# OOBDpiZero.net
KiCad netlist of a schematic drawn in EAGLE
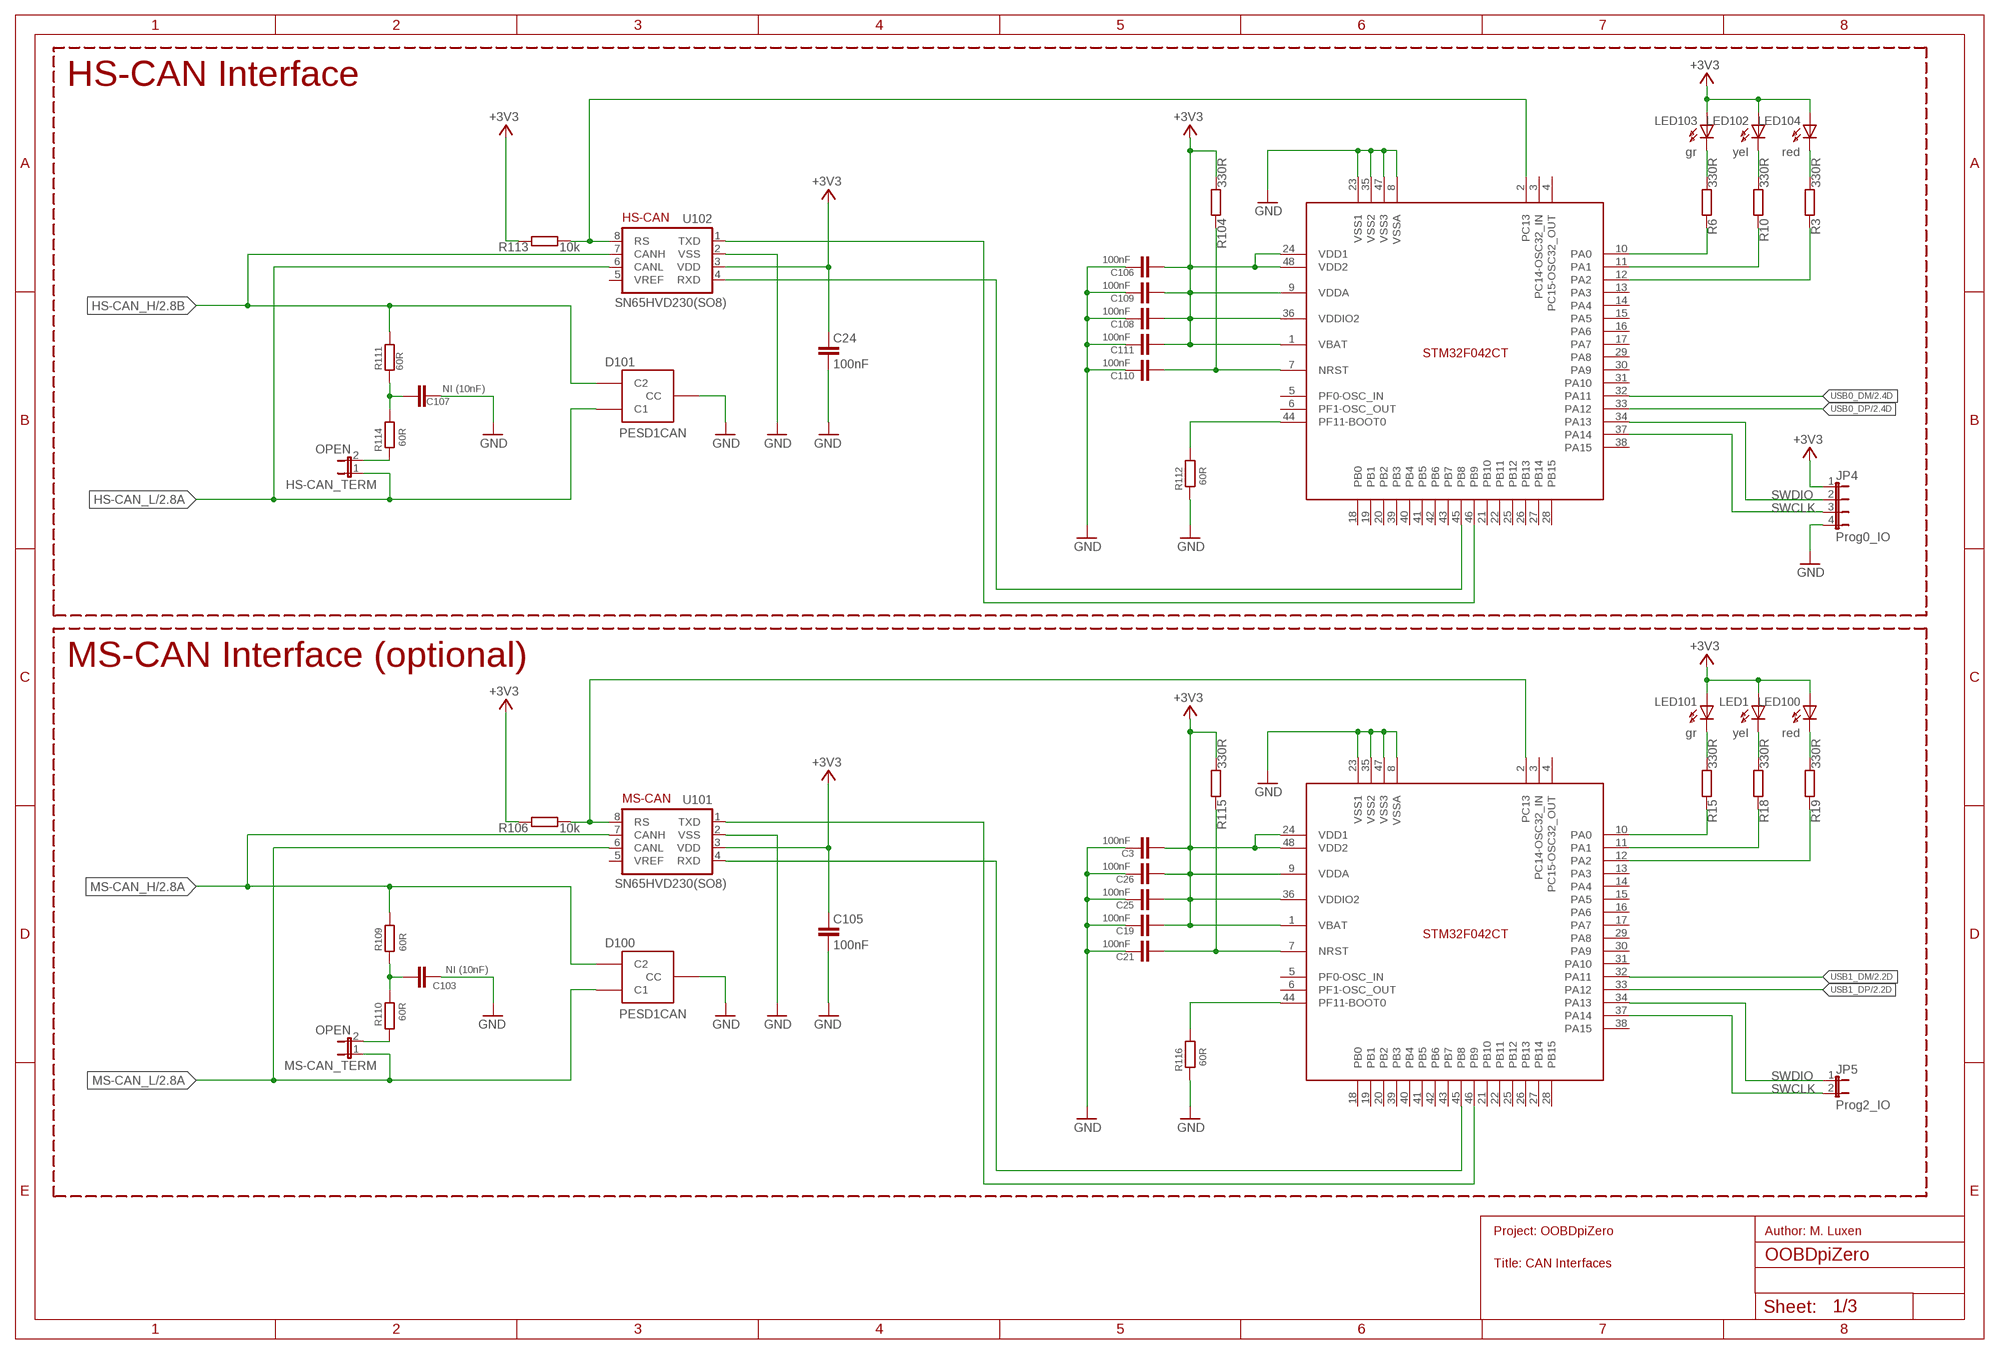
[diagram p0: schematic, sheet 1]
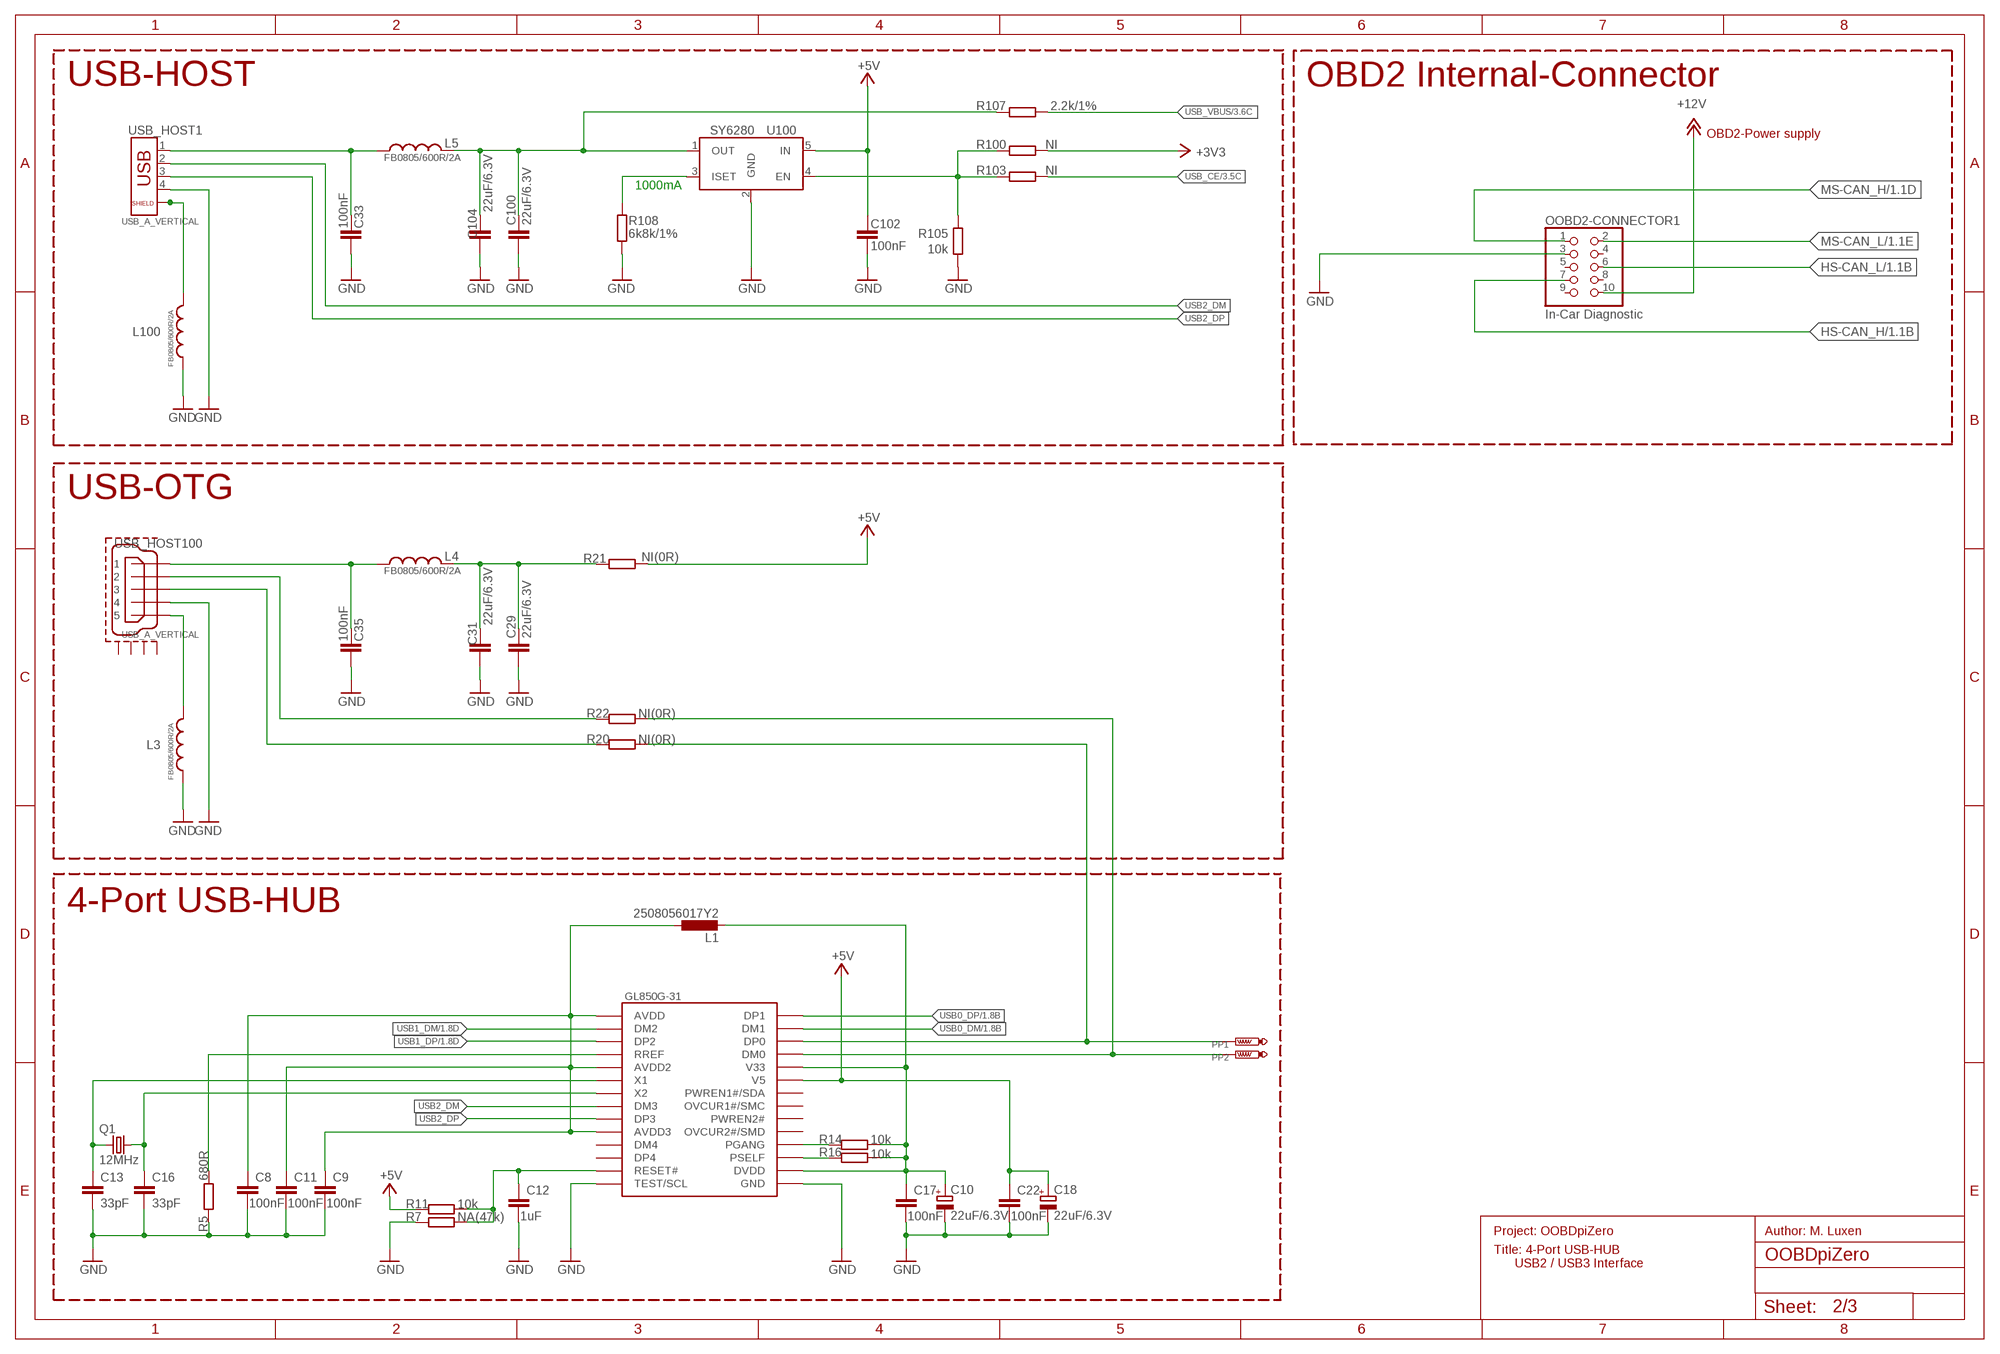
[diagram p1: schematic, sheet 2]
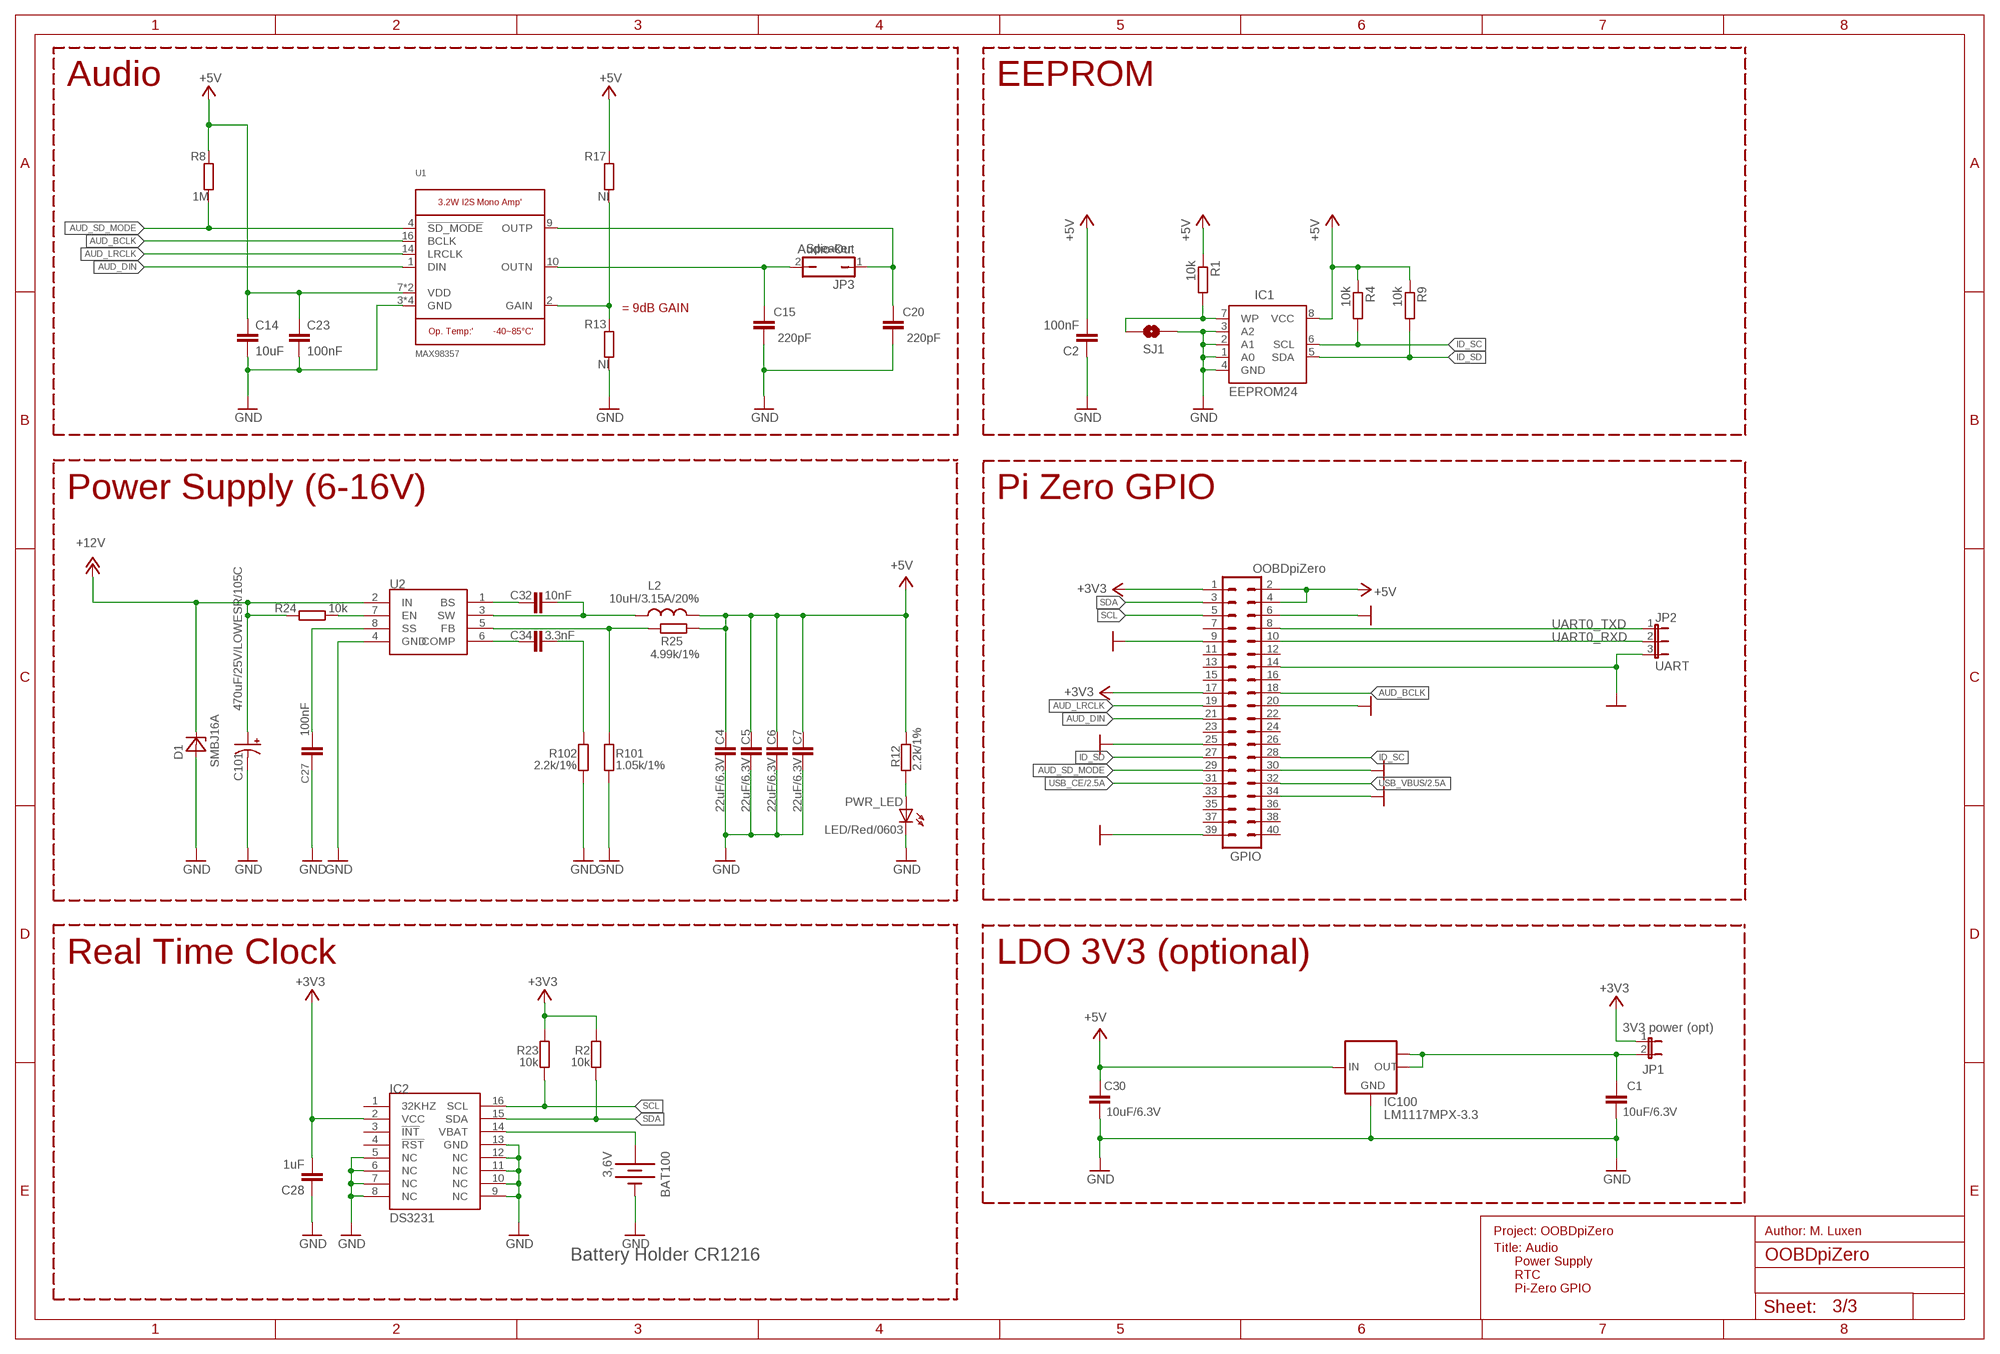
[diagram p2: schematic, sheet 3]

(export (version "E")
  (design (tool "Eeschema 10.0.6"))
  (components
    (comp (ref "BAT100")
      (value "3,6V")
      (footprint "eagle-import:BATTCON_12MM_PTH")
      (libsource (lib "eagle-import") (part "BATTERY12PTH"))
    )
    (comp (ref "C1")
      (value "10uF/6.3V")
      (footprint "eagle-import:C0603")
      (libsource (lib "eagle-import") (part "C-EUC0603"))
    )
    (comp (ref "C2")
      (value "100nF")
      (footprint "eagle-import:C0603")
      (libsource (lib "eagle-import") (part "C-EUC0603"))
    )
    (comp (ref "C4")
      (value "22uF/6.3V")
      (footprint "eagle-import:C0603")
      (libsource (lib "eagle-import") (part "C-EUC0603"))
    )
    (comp (ref "C5")
      (value "22uF/6.3V")
      (footprint "eagle-import:C0603")
      (libsource (lib "eagle-import") (part "C-EUC0603"))
    )
    (comp (ref "C6")
      (value "22uF/6.3V")
      (footprint "eagle-import:C0603")
      (libsource (lib "eagle-import") (part "C-EUC0603"))
    )
    (comp (ref "C7")
      (value "22uF/6.3V")
      (footprint "eagle-import:C0603")
      (libsource (lib "eagle-import") (part "C-EUC0603"))
    )
    (comp (ref "C14")
      (value "10uF")
      (footprint "eagle-import:C0805K")
      (libsource (lib "eagle-import") (part "C-EUC0805K"))
    )
    (comp (ref "C15")
      (value "220pF")
      (footprint "eagle-import:C0603K")
      (libsource (lib "eagle-import") (part "C-EUC0603K"))
    )
    (comp (ref "C20")
      (value "220pF")
      (footprint "eagle-import:C0603K")
      (libsource (lib "eagle-import") (part "C-EUC0603K"))
    )
    (comp (ref "C23")
      (value "100nF")
      (footprint "eagle-import:C0603K")
      (libsource (lib "eagle-import") (part "C-EUC0603K"))
    )
    (comp (ref "C27")
      (value "100nF")
      (footprint "eagle-import:C0603")
      (libsource (lib "eagle-import") (part "C-EUC0603"))
    )
    (comp (ref "C28")
      (value "1uF")
      (footprint "eagle-import:C0603")
      (libsource (lib "eagle-import") (part "C-EUC0603"))
    )
    (comp (ref "C30")
      (value "10uF/6.3V")
      (footprint "eagle-import:C0603")
      (libsource (lib "eagle-import") (part "C-EUC0603"))
    )
    (comp (ref "C32")
      (value "10nF")
      (footprint "eagle-import:C0603")
      (libsource (lib "eagle-import") (part "C-EUC0603"))
    )
    (comp (ref "C34")
      (value "3.3nF")
      (footprint "eagle-import:C0603")
      (libsource (lib "eagle-import") (part "C-EUC0603"))
    )
    (comp (ref "C101")
      (value "470uF/25V/LOWESR/105C")
      (footprint "eagle-import:PANASONIC_D")
      (libsource (lib "eagle-import") (part "47UF-50V-20%(ELECT)"))
    )
    (comp (ref "D1")
      (value "SMBJ16A")
      (footprint "eagle-import:DO214AA")
      (libsource (lib "eagle-import") (part "SMBJ16A"))
    )
    (comp (ref "GPIO")
      (value "OOBDpiZero")
      (footprint "eagle-import:PIZERO_THOUGH_HOLE")
      (libsource (lib "eagle-import") (part "PIZERO_THROUGH_HOLE"))
    )
    (comp (ref "IC1")
      (value "EEPROM24")
      (footprint "eagle-import:SOIC8")
      (libsource (lib "eagle-import") (part "EEPROM24"))
    )
    (comp (ref "IC2")
      (value "DS3231")
      (footprint "eagle-import:SOIC-16W")
      (libsource (lib "eagle-import") (part "DS3231SOIC-16W"))
    )
    (comp (ref "IC100")
      (value "LM1117MPX-3.3")
      (footprint "eagle-import:SOT223")
      (libsource (lib "eagle-import") (part "LM1117MPX-3.3"))
    )
    (comp (ref "JP1")
      (value "3V3 power (opt)")
      (footprint "eagle-import:JP1")
      (libsource (lib "eagle-import") (part "JP1E"))
    )
    (comp (ref "JP2")
      (value "UART")
      (footprint "eagle-import:JP2")
      (libsource (lib "eagle-import") (part "JP2E"))
    )
    (comp (ref "JP3")
      (value "Audio-Out")
      (footprint "eagle-import:JP1")
      (libsource (lib "eagle-import") (part "JP1Q"))
    )
    (comp (ref "L2")
      (value "10uH/3.15A/20%")
      (footprint "eagle-import:8X8MM_3131")
      (libsource (lib "eagle-import") (part "LLQH88PN100M38"))
    )
    (comp (ref "PWR_LED")
      (value "LED/Red/0603")
      (footprint "eagle-import:LED-0603")
      (libsource (lib "eagle-import") (part "LED0603DWS"))
    )
    (comp (ref "R1")
      (value "10k")
      (footprint "eagle-import:R0603")
      (libsource (lib "eagle-import") (part "R-EU_R0603"))
    )
    (comp (ref "R2")
      (value "10k")
      (footprint "eagle-import:R0603")
      (libsource (lib "eagle-import") (part "R-EU_R0603"))
    )
    (comp (ref "R4")
      (value "10k")
      (footprint "eagle-import:R0603")
      (libsource (lib "eagle-import") (part "R-EU_R0603"))
    )
    (comp (ref "R8")
      (value "1M")
      (footprint "eagle-import:R0603")
      (libsource (lib "eagle-import") (part "resistor_R-EU_R0603"))
    )
    (comp (ref "R9")
      (value "10k")
      (footprint "eagle-import:R0603")
      (libsource (lib "eagle-import") (part "R-EU_R0603"))
    )
    (comp (ref "R12")
      (value "2.2k/1%")
      (footprint "eagle-import:R0603")
      (libsource (lib "eagle-import") (part "R-EU_R0603"))
    )
    (comp (ref "R13")
      (value "NI")
      (footprint "eagle-import:R0603")
      (libsource (lib "eagle-import") (part "resistor_R-EU_R0603"))
    )
    (comp (ref "R17")
      (value "NI")
      (footprint "eagle-import:R0603")
      (libsource (lib "eagle-import") (part "resistor_R-EU_R0603"))
    )
    (comp (ref "R23")
      (value "10k")
      (footprint "eagle-import:R0603")
      (libsource (lib "eagle-import") (part "R-EU_R0603"))
    )
    (comp (ref "R24")
      (value "10k")
      (footprint "eagle-import:R0603")
      (libsource (lib "eagle-import") (part "R-EU_R0603"))
    )
    (comp (ref "R25")
      (value "4.99k/1%")
      (footprint "eagle-import:R0603")
      (libsource (lib "eagle-import") (part "R-EU_R0603"))
    )
    (comp (ref "R101")
      (value "1.05k/1%")
      (footprint "eagle-import:R0603")
      (libsource (lib "eagle-import") (part "R-EU_R0603"))
    )
    (comp (ref "R102")
      (value "2.2k/1%")
      (footprint "eagle-import:R0603")
      (libsource (lib "eagle-import") (part "R-EU_R0603"))
    )
    (comp (ref "SJ1")
      (value "SOLDERJUMPERTRACE")
      (footprint "eagle-import:SJ_2S-TRACE")
      (libsource (lib "eagle-import") (part "SOLDERJUMPERTRACE"))
    )
    (comp (ref "U1")
      (value "MAX98357")
      (footprint "eagle-import:QFN16_3MM")
      (libsource (lib "eagle-import") (part "AUDIOAMP_MAX98357"))
    )
    (comp (ref "U2")
      (value "MP1482")
      (footprint "eagle-import:SOIC8")
      (libsource (lib "eagle-import") (part "MP1482"))
    )
    (comp (ref "C8")
      (value "100nF")
      (footprint "eagle-import:C0603")
      (libsource (lib "eagle-import") (part "resistor_C-EUC0603"))
    )
    (comp (ref "C9")
      (value "100nF")
      (footprint "eagle-import:C0603")
      (libsource (lib "eagle-import") (part "resistor_C-EUC0603"))
    )
    (comp (ref "C10")
      (value "22uF/6.3V")
      (footprint "eagle-import:SMC_A")
      (libsource (lib "eagle-import") (part "CPOL-EUSMCA"))
    )
    (comp (ref "C11")
      (value "100nF")
      (footprint "eagle-import:C0603")
      (libsource (lib "eagle-import") (part "resistor_C-EUC0603"))
    )
    (comp (ref "C12")
      (value "1uF")
      (footprint "eagle-import:C0603")
      (libsource (lib "eagle-import") (part "resistor_C-EUC0603"))
    )
    (comp (ref "C13")
      (value "33pF")
      (footprint "eagle-import:C0603")
      (libsource (lib "eagle-import") (part "resistor_C-EUC0603"))
    )
    (comp (ref "C16")
      (value "33pF")
      (footprint "eagle-import:C0603")
      (libsource (lib "eagle-import") (part "resistor_C-EUC0603"))
    )
    (comp (ref "C17")
      (value "100nF")
      (footprint "eagle-import:C0603")
      (libsource (lib "eagle-import") (part "resistor_C-EUC0603"))
    )
    (comp (ref "C18")
      (value "22uF/6.3V")
      (footprint "eagle-import:SMC_A")
      (libsource (lib "eagle-import") (part "CPOL-EUSMCA"))
    )
    (comp (ref "C22")
      (value "100nF")
      (footprint "eagle-import:C0603")
      (libsource (lib "eagle-import") (part "resistor_C-EUC0603"))
    )
    (comp (ref "C29")
      (value "22uF/6.3V")
      (footprint "eagle-import:C0603")
      (libsource (lib "eagle-import") (part "C-EUC0603"))
    )
    (comp (ref "C31")
      (value "22uF/6.3V")
      (footprint "eagle-import:C0603")
      (libsource (lib "eagle-import") (part "C-EUC0603"))
    )
    (comp (ref "C33")
      (value "100nF")
      (footprint "eagle-import:C0603K")
      (libsource (lib "eagle-import") (part "C-EUC0603K"))
    )
    (comp (ref "C35")
      (value "100nF")
      (footprint "eagle-import:C0603K")
      (libsource (lib "eagle-import") (part "C-EUC0603K"))
    )
    (comp (ref "C100")
      (value "22uF/6.3V")
      (footprint "eagle-import:C0603")
      (libsource (lib "eagle-import") (part "C-EUC0603"))
    )
    (comp (ref "C102")
      (value "100nF")
      (footprint "eagle-import:C0603K")
      (libsource (lib "eagle-import") (part "C-EUC0603K"))
    )
    (comp (ref "C104")
      (value "22uF/6.3V")
      (footprint "eagle-import:C0603")
      (libsource (lib "eagle-import") (part "C-EUC0603"))
    )
    (comp (ref "L1")
      (value "2508056017Y2")
      (footprint "eagle-import:L0805@1")
      (libsource (lib "eagle-import") (part "L-EUL0805"))
    )
    (comp (ref "L3")
      (value "FB0805/600R/2A")
      (footprint "eagle-import:L0603")
      (libsource (lib "eagle-import") (part "L-USL0603"))
    )
    (comp (ref "L4")
      (value "FB0805/600R/2A")
      (footprint "eagle-import:L0603")
      (libsource (lib "eagle-import") (part "L-USL0603"))
    )
    (comp (ref "L5")
      (value "FB0805/600R/2A")
      (footprint "eagle-import:L0603")
      (libsource (lib "eagle-import") (part "L-USL0603"))
    )
    (comp (ref "L100")
      (value "FB0805/600R/2A")
      (footprint "eagle-import:L0603")
      (libsource (lib "eagle-import") (part "L-USL0603"))
    )
    (comp (ref "OOBD2-CONNECTOR1")
      (value "In-Car Diagnostic")
      (footprint "eagle-import:2X05_90")
      (libsource (lib "eagle-import") (part "PINHD-2X5/90"))
    )
    (comp (ref "PP1")
      (value "PTR1PAD1-11")
      (footprint "eagle-import:P1-11")
      (libsource (lib "eagle-import") (part "PTR1PAD1-11"))
    )
    (comp (ref "PP2")
      (value "PTR1PAD1-11")
      (footprint "eagle-import:P1-11")
      (libsource (lib "eagle-import") (part "PTR1PAD1-11"))
    )
    (comp (ref "Q1")
      (value "12MHz")
      (footprint "eagle-import:SM49")
      (libsource (lib "eagle-import") (part "CRYSTALSM49"))
    )
    (comp (ref "R5")
      (value "680R")
      (footprint "eagle-import:R0603")
      (libsource (lib "eagle-import") (part "resistor_R-EU_R0603"))
    )
    (comp (ref "R7")
      (value "NA(47k)")
      (footprint "eagle-import:R0603")
      (libsource (lib "eagle-import") (part "resistor_R-EU_R0603"))
    )
    (comp (ref "R11")
      (value "10k")
      (footprint "eagle-import:R0603")
      (libsource (lib "eagle-import") (part "resistor_R-EU_R0603"))
    )
    (comp (ref "R14")
      (value "10k")
      (footprint "eagle-import:R0603")
      (libsource (lib "eagle-import") (part "resistor_R-EU_R0603"))
    )
    (comp (ref "R16")
      (value "10k")
      (footprint "eagle-import:R0603")
      (libsource (lib "eagle-import") (part "resistor_R-EU_R0603"))
    )
    (comp (ref "R20")
      (value "NI(0R)")
      (footprint "eagle-import:R0603")
      (libsource (lib "eagle-import") (part "resistor_R-EU_R0603"))
    )
    (comp (ref "R21")
      (value "NI(0R)")
      (footprint "eagle-import:R0805")
      (libsource (lib "eagle-import") (part "resistor_R-EU_R0805"))
    )
    (comp (ref "R22")
      (value "NI(0R)")
      (footprint "eagle-import:R0603")
      (libsource (lib "eagle-import") (part "resistor_R-EU_R0603"))
    )
    (comp (ref "R100")
      (value "NI")
      (footprint "eagle-import:R0603")
      (libsource (lib "eagle-import") (part "R-EU_R0603"))
    )
    (comp (ref "R103")
      (value "NI")
      (footprint "eagle-import:R0603")
      (libsource (lib "eagle-import") (part "R-EU_R0603"))
    )
    (comp (ref "R105")
      (value "10k")
      (footprint "eagle-import:R0603")
      (libsource (lib "eagle-import") (part "R-EU_R0603"))
    )
    (comp (ref "R107")
      (value "2.2k/1%")
      (footprint "eagle-import:R0603")
      (libsource (lib "eagle-import") (part "R-EU_R0603"))
    )
    (comp (ref "R108")
      (value "6k8k/1%")
      (footprint "eagle-import:R0603")
      (libsource (lib "eagle-import") (part "R-EU_R0603"))
    )
    (comp (ref "U$101")
      (value "GL850G-31")
      (footprint "eagle-import:TSSOP28")
      (libsource (lib "eagle-import") (part "GL850G-31"))
    )
    (comp (ref "U100")
      (value "SY6280")
      (footprint "eagle-import:SOT23-5")
      (libsource (lib "eagle-import") (part "SY6280"))
    )
    (comp (ref "USB_HOST1")
      (value "USB_A_VERTICAL")
      (footprint "eagle-import:USB_PN87520_DEV_PTH")
      (libsource (lib "eagle-import") (part "USB_SHIELD1"))
    )
    (comp (ref "USB_HOST100")
      (value "USB_A_VERTICAL")
      (footprint "eagle-import:47589-0001")
      (libsource (lib "eagle-import") (part "MICRO-USB-RECEPTACLE47589-0001"))
    )
    (comp (ref "C3")
      (value "100nF")
      (footprint "eagle-import:C0603")
      (libsource (lib "eagle-import") (part "resistor_C-EUC0603"))
    )
    (comp (ref "C19")
      (value "100nF")
      (footprint "eagle-import:C0603")
      (libsource (lib "eagle-import") (part "resistor_C-EUC0603"))
    )
    (comp (ref "C21")
      (value "100nF")
      (footprint "eagle-import:C0603")
      (libsource (lib "eagle-import") (part "resistor_C-EUC0603"))
    )
    (comp (ref "C24")
      (value "100nF")
      (footprint "eagle-import:C0603K")
      (libsource (lib "eagle-import") (part "C-EUC0603K"))
    )
    (comp (ref "C25")
      (value "100nF")
      (footprint "eagle-import:C0603")
      (libsource (lib "eagle-import") (part "resistor_C-EUC0603"))
    )
    (comp (ref "C26")
      (value "100nF")
      (footprint "eagle-import:C0603")
      (libsource (lib "eagle-import") (part "resistor_C-EUC0603"))
    )
    (comp (ref "C103")
      (value "NI (10nF)")
      (footprint "eagle-import:C0603")
      (libsource (lib "eagle-import") (part "resistor_C-EUC0603"))
    )
    (comp (ref "C105")
      (value "100nF")
      (footprint "eagle-import:C0603K")
      (libsource (lib "eagle-import") (part "C-EUC0603K"))
    )
    (comp (ref "C106")
      (value "100nF")
      (footprint "eagle-import:C0603")
      (libsource (lib "eagle-import") (part "resistor_C-EUC0603"))
    )
    (comp (ref "C107")
      (value "NI (10nF)")
      (footprint "eagle-import:C0603")
      (libsource (lib "eagle-import") (part "resistor_C-EUC0603"))
    )
    (comp (ref "C108")
      (value "100nF")
      (footprint "eagle-import:C0603")
      (libsource (lib "eagle-import") (part "resistor_C-EUC0603"))
    )
    (comp (ref "C109")
      (value "100nF")
      (footprint "eagle-import:C0603")
      (libsource (lib "eagle-import") (part "resistor_C-EUC0603"))
    )
    (comp (ref "C110")
      (value "100nF")
      (footprint "eagle-import:C0603")
      (libsource (lib "eagle-import") (part "resistor_C-EUC0603"))
    )
    (comp (ref "C111")
      (value "100nF")
      (footprint "eagle-import:C0603")
      (libsource (lib "eagle-import") (part "resistor_C-EUC0603"))
    )
    (comp (ref "D100")
      (value "PESD1CAN")
      (footprint "eagle-import:SOT23")
      (libsource (lib "eagle-import") (part "PESD1CAN"))
    )
    (comp (ref "D101")
      (value "PESD1CAN")
      (footprint "eagle-import:SOT23")
      (libsource (lib "eagle-import") (part "PESD1CAN"))
    )
    (comp (ref "HS-CAN_TERM")
      (value "OPEN")
      (footprint "eagle-import:1X02")
      (libsource (lib "eagle-import") (part "JUMPER-2PTH"))
    )
    (comp (ref "JP4")
      (value "Prog0_IO")
      (footprint "eagle-import:JP4")
      (libsource (lib "eagle-import") (part "JP4E"))
    )
    (comp (ref "JP5")
      (value "Prog2_IO")
      (footprint "eagle-import:JP1")
      (libsource (lib "eagle-import") (part "JP1E"))
    )
    (comp (ref "LED1")
      (value "yel")
      (footprint "eagle-import:LED_0603")
      (libsource (lib "eagle-import") (part "LEDLED_0603"))
    )
    (comp (ref "LED100")
      (value "red")
      (footprint "eagle-import:LED_0603")
      (libsource (lib "eagle-import") (part "LEDLED_0603"))
    )
    (comp (ref "LED101")
      (value "gr")
      (footprint "eagle-import:LED_0603")
      (libsource (lib "eagle-import") (part "LEDLED_0603"))
    )
    (comp (ref "LED102")
      (value "yel")
      (footprint "eagle-import:LED_0603")
      (libsource (lib "eagle-import") (part "LEDLED_0603"))
    )
    (comp (ref "LED103")
      (value "gr")
      (footprint "eagle-import:LED_0603")
      (libsource (lib "eagle-import") (part "LEDLED_0603"))
    )
    (comp (ref "LED104")
      (value "red")
      (footprint "eagle-import:LED_0603")
      (libsource (lib "eagle-import") (part "LEDLED_0603"))
    )
    (comp (ref "MS-CAN_TERM")
      (value "OPEN")
      (footprint "eagle-import:1X02")
      (libsource (lib "eagle-import") (part "JUMPER-2PTH"))
    )
    (comp (ref "R3")
      (value "330R")
      (footprint "eagle-import:R0603")
      (libsource (lib "eagle-import") (part "R-EU_R0603"))
    )
    (comp (ref "R6")
      (value "330R")
      (footprint "eagle-import:R0603")
      (libsource (lib "eagle-import") (part "R-EU_R0603"))
    )
    (comp (ref "R10")
      (value "330R")
      (footprint "eagle-import:R0603")
      (libsource (lib "eagle-import") (part "R-EU_R0603"))
    )
    (comp (ref "R15")
      (value "330R")
      (footprint "eagle-import:R0603")
      (libsource (lib "eagle-import") (part "R-EU_R0603"))
    )
    (comp (ref "R18")
      (value "330R")
      (footprint "eagle-import:R0603")
      (libsource (lib "eagle-import") (part "R-EU_R0603"))
    )
    (comp (ref "R19")
      (value "330R")
      (footprint "eagle-import:R0603")
      (libsource (lib "eagle-import") (part "R-EU_R0603"))
    )
    (comp (ref "R104")
      (value "330R")
      (footprint "eagle-import:R0603")
      (libsource (lib "eagle-import") (part "R-EU_R0603"))
    )
    (comp (ref "R106")
      (value "10k")
      (footprint "eagle-import:R0603")
      (libsource (lib "eagle-import") (part "R-EU_R0603"))
    )
    (comp (ref "R109")
      (value "60R")
      (footprint "eagle-import:R0603")
      (libsource (lib "eagle-import") (part "resistor_R-EU_R0603"))
    )
    (comp (ref "R110")
      (value "60R")
      (footprint "eagle-import:R0603")
      (libsource (lib "eagle-import") (part "resistor_R-EU_R0603"))
    )
    (comp (ref "R111")
      (value "60R")
      (footprint "eagle-import:R0603")
      (libsource (lib "eagle-import") (part "resistor_R-EU_R0603"))
    )
    (comp (ref "R112")
      (value "60R")
      (footprint "eagle-import:R0603")
      (libsource (lib "eagle-import") (part "resistor_R-EU_R0603"))
    )
    (comp (ref "R113")
      (value "10k")
      (footprint "eagle-import:R0603")
      (libsource (lib "eagle-import") (part "R-EU_R0603"))
    )
    (comp (ref "R114")
      (value "60R")
      (footprint "eagle-import:R0603")
      (libsource (lib "eagle-import") (part "resistor_R-EU_R0603"))
    )
    (comp (ref "R115")
      (value "330R")
      (footprint "eagle-import:R0603")
      (libsource (lib "eagle-import") (part "R-EU_R0603"))
    )
    (comp (ref "R116")
      (value "60R")
      (footprint "eagle-import:R0603")
      (libsource (lib "eagle-import") (part "resistor_R-EU_R0603"))
    )
    (comp (ref "U$100")
      (value "STM32F042CT")
      (footprint "eagle-import:LQFP48")
      (libsource (lib "eagle-import") (part "STM32F042CT"))
    )
    (comp (ref "U$102")
      (value "STM32F042CT")
      (footprint "eagle-import:LQFP48")
      (libsource (lib "eagle-import") (part "STM32F042CT"))
    )
    (comp (ref "U101")
      (value "SN65HVD230(SO8)")
      (footprint "eagle-import:SO-08")
      (libsource (lib "eagle-import") (part "MCP2551"))
    )
    (comp (ref "U102")
      (value "SN65HVD230(SO8)")
      (footprint "eagle-import:SO-08")
      (libsource (lib "eagle-import") (part "MCP2551"))
    )
  )
  (nets
    (net (code "1") (name "+3V3") (class "Default")
      (node (ref "C105") (pin "1") (pinfunction "1_1") (pintype "passive"))
      (node (ref "C106") (pin "2") (pinfunction "2_2") (pintype "passive"))
      (node (ref "C108") (pin "2") (pinfunction "2_2") (pintype "passive"))
      (node (ref "C109") (pin "2") (pinfunction "2_2") (pintype "passive"))
      (node (ref "C111") (pin "2") (pinfunction "2_2") (pintype "passive"))
      (node (ref "C19") (pin "2") (pinfunction "2_2") (pintype "passive"))
      (node (ref "C24") (pin "1") (pinfunction "1_1") (pintype "passive"))
      (node (ref "C25") (pin "2") (pinfunction "2_2") (pintype "passive"))
      (node (ref "C26") (pin "2") (pinfunction "2_2") (pintype "passive"))
      (node (ref "C28") (pin "2") (pinfunction "2_2") (pintype "passive"))
      (node (ref "C3") (pin "2") (pinfunction "2_2") (pintype "passive"))
      (node (ref "GPIO") (pin "1") (pinfunction "1_1") (pintype "passive"))
      (node (ref "GPIO") (pin "17") (pinfunction "17_17") (pintype "passive"))
      (node (ref "IC2") (pin "2") (pinfunction "VCC_2") (pintype "bidirectional"))
      (node (ref "JP1") (pin "1") (pinfunction "1_1") (pintype "passive"))
      (node (ref "JP4") (pin "1") (pinfunction "1_1") (pintype "passive"))
      (node (ref "LED1") (pin "A") (pinfunction "A_A") (pintype "passive"))
      (node (ref "LED100") (pin "A") (pinfunction "A_A") (pintype "passive"))
      (node (ref "LED101") (pin "A") (pinfunction "A_A") (pintype "passive"))
      (node (ref "LED102") (pin "A") (pinfunction "A_A") (pintype "passive"))
      (node (ref "LED103") (pin "A") (pinfunction "A_A") (pintype "passive"))
      (node (ref "LED104") (pin "A") (pinfunction "A_A") (pintype "passive"))
      (node (ref "R100") (pin "2") (pinfunction "2_2") (pintype "passive"))
      (node (ref "R104") (pin "1") (pinfunction "1_1") (pintype "passive"))
      (node (ref "R106") (pin "2") (pinfunction "2_2") (pintype "passive"))
      (node (ref "R113") (pin "2") (pinfunction "2_2") (pintype "passive"))
      (node (ref "R115") (pin "1") (pinfunction "1_1") (pintype "passive"))
      (node (ref "R2") (pin "1") (pinfunction "1_1") (pintype "passive"))
      (node (ref "R23") (pin "1") (pinfunction "1_1") (pintype "passive"))
      (node (ref "U$100") (pin "1") (pinfunction "VBAT_1") (pintype "power_in"))
      (node (ref "U$100") (pin "24") (pinfunction "VDD1_24") (pintype "power_in"))
      (node (ref "U$100") (pin "36") (pinfunction "VDDIO2_36") (pintype "power_in"))
      (node (ref "U$100") (pin "48") (pinfunction "VDD2_48") (pintype "power_in"))
      (node (ref "U$100") (pin "9") (pinfunction "VDDA_9") (pintype "power_in"))
      (node (ref "U$102") (pin "1") (pinfunction "VBAT_1") (pintype "power_in"))
      (node (ref "U$102") (pin "24") (pinfunction "VDD1_24") (pintype "power_in"))
      (node (ref "U$102") (pin "36") (pinfunction "VDDIO2_36") (pintype "power_in"))
      (node (ref "U$102") (pin "48") (pinfunction "VDD2_48") (pintype "power_in"))
      (node (ref "U$102") (pin "9") (pinfunction "VDDA_9") (pintype "power_in"))
      (node (ref "U101") (pin "3") (pinfunction "VDD_3") (pintype "power_in"))
      (node (ref "U102") (pin "3") (pinfunction "VDD_3") (pintype "power_in"))
    )
    (net (code "2") (name "+5V") (class "Default")
      (node (ref "C102") (pin "1") (pinfunction "1_1") (pintype "passive"))
      (node (ref "C14") (pin "1") (pinfunction "1_1") (pintype "passive"))
      (node (ref "C18") (pin "+") (pinfunction "+_+") (pintype "passive"))
      (node (ref "C2") (pin "2") (pinfunction "2_2") (pintype "passive"))
      (node (ref "C22") (pin "1") (pinfunction "1_1") (pintype "passive"))
      (node (ref "C23") (pin "1") (pinfunction "1_1") (pintype "passive"))
      (node (ref "C30") (pin "1") (pinfunction "1_1") (pintype "passive"))
      (node (ref "C4") (pin "1") (pinfunction "1_1") (pintype "passive"))
      (node (ref "C5") (pin "1") (pinfunction "1_1") (pintype "passive"))
      (node (ref "C6") (pin "1") (pinfunction "1_1") (pintype "passive"))
      (node (ref "C7") (pin "1") (pinfunction "1_1") (pintype "passive"))
      (node (ref "GPIO") (pin "2") (pinfunction "2_2") (pintype "passive"))
      (node (ref "GPIO") (pin "4") (pinfunction "4_4") (pintype "passive"))
      (node (ref "IC1") (pin "8") (pinfunction "VCC_8") (pintype "power_in"))
      (node (ref "IC100") (pin "3") (pinfunction "IN_3") (pintype "input"))
      (node (ref "L2") (pin "2") (pinfunction "2_2") (pintype "passive"))
      (node (ref "R1") (pin "1") (pinfunction "1_1") (pintype "passive"))
      (node (ref "R11") (pin "1") (pinfunction "1_1") (pintype "passive"))
      (node (ref "R12") (pin "1") (pinfunction "1_1") (pintype "passive"))
      (node (ref "R17") (pin "2") (pinfunction "2_2") (pintype "passive"))
      (node (ref "R21") (pin "2") (pinfunction "2_2") (pintype "passive"))
      (node (ref "R25") (pin "2") (pinfunction "2_2") (pintype "passive"))
      (node (ref "R4") (pin "1") (pinfunction "1_1") (pintype "passive"))
      (node (ref "R8") (pin "2") (pinfunction "2_2") (pintype "passive"))
      (node (ref "R9") (pin "1") (pinfunction "1_1") (pintype "passive"))
      (node (ref "U$101") (pin "23") (pinfunction "V5_23") (pintype "bidirectional"))
      (node (ref "U1") (pin "7") (pinfunction "VDD_7") (pintype "power_in"))
      (node (ref "U1") (pin "8") (pinfunction "VDD_8") (pintype "power_in"))
      (node (ref "U100") (pin "5") (pinfunction "IN_5") (pintype "power_in"))
    )
    (net (code "3") (name "+12V") (class "Default")
      (node (ref "C101") (pin "+") (pinfunction "+_+") (pintype "passive"))
      (node (ref "D1") (pin "C") (pinfunction "C_C") (pintype "passive"))
      (node (ref "OOBD2-CONNECTOR1") (pin "10") (pinfunction "10_10") (pintype "passive"))
      (node (ref "R24") (pin "1") (pinfunction "1_1") (pintype "passive"))
      (node (ref "U2") (pin "2") (pinfunction "IN_2") (pintype "bidirectional"))
    )
    (net (code "4") (name "AUD_BCLK") (class "Default")
      (node (ref "GPIO") (pin "18") (pinfunction "18_18") (pintype "passive"))
      (node (ref "U1") (pin "16") (pinfunction "BCLK_16") (pintype "bidirectional"))
    )
    (net (code "5") (name "AUD_DIN") (class "Default")
      (node (ref "GPIO") (pin "21") (pinfunction "21_21") (pintype "passive"))
      (node (ref "U1") (pin "1") (pinfunction "DIN_1") (pintype "bidirectional"))
    )
    (net (code "6") (name "AUD_LRCLK") (class "Default")
      (node (ref "GPIO") (pin "19") (pinfunction "19_19") (pintype "passive"))
      (node (ref "U1") (pin "14") (pinfunction "LRCLK_14") (pintype "bidirectional"))
    )
    (net (code "7") (name "AUD_SD_MODE") (class "Default")
      (node (ref "GPIO") (pin "29") (pinfunction "29_29") (pintype "passive"))
      (node (ref "R8") (pin "1") (pinfunction "1_1") (pintype "passive"))
      (node (ref "U1") (pin "4") (pinfunction "~{SD_MODE}_4") (pintype "bidirectional"))
    )
    (net (code "8") (name "GND") (class "Default")
      (node (ref "BAT100") (pin "GND") (pinfunction "-_GND") (pintype "power_in"))
      (node (ref "C1") (pin "2") (pinfunction "2_2") (pintype "passive"))
      (node (ref "C10") (pin "-") (pinfunction "-_-") (pintype "passive"))
      (node (ref "C100") (pin "2") (pinfunction "2_2") (pintype "passive"))
      (node (ref "C101") (pin "-") (pinfunction "-_-") (pintype "passive"))
      (node (ref "C102") (pin "2") (pinfunction "2_2") (pintype "passive"))
      (node (ref "C103") (pin "2") (pinfunction "2_2") (pintype "passive"))
      (node (ref "C104") (pin "2") (pinfunction "2_2") (pintype "passive"))
      (node (ref "C105") (pin "2") (pinfunction "2_2") (pintype "passive"))
      (node (ref "C106") (pin "1") (pinfunction "1_1") (pintype "passive"))
      (node (ref "C107") (pin "2") (pinfunction "2_2") (pintype "passive"))
      (node (ref "C108") (pin "1") (pinfunction "1_1") (pintype "passive"))
      (node (ref "C109") (pin "1") (pinfunction "1_1") (pintype "passive"))
      (node (ref "C11") (pin "2") (pinfunction "2_2") (pintype "passive"))
      (node (ref "C110") (pin "1") (pinfunction "1_1") (pintype "passive"))
      (node (ref "C111") (pin "1") (pinfunction "1_1") (pintype "passive"))
      (node (ref "C12") (pin "2") (pinfunction "2_2") (pintype "passive"))
      (node (ref "C13") (pin "2") (pinfunction "2_2") (pintype "passive"))
      (node (ref "C14") (pin "2") (pinfunction "2_2") (pintype "passive"))
      (node (ref "C15") (pin "1") (pinfunction "1_1") (pintype "passive"))
      (node (ref "C16") (pin "2") (pinfunction "2_2") (pintype "passive"))
      (node (ref "C17") (pin "2") (pinfunction "2_2") (pintype "passive"))
      (node (ref "C18") (pin "-") (pinfunction "-_-") (pintype "passive"))
      (node (ref "C19") (pin "1") (pinfunction "1_1") (pintype "passive"))
      (node (ref "C2") (pin "1") (pinfunction "1_1") (pintype "passive"))
      (node (ref "C20") (pin "1") (pinfunction "1_1") (pintype "passive"))
      (node (ref "C21") (pin "1") (pinfunction "1_1") (pintype "passive"))
      (node (ref "C22") (pin "2") (pinfunction "2_2") (pintype "passive"))
      (node (ref "C23") (pin "2") (pinfunction "2_2") (pintype "passive"))
      (node (ref "C24") (pin "2") (pinfunction "2_2") (pintype "passive"))
      (node (ref "C25") (pin "1") (pinfunction "1_1") (pintype "passive"))
      (node (ref "C26") (pin "1") (pinfunction "1_1") (pintype "passive"))
      (node (ref "C27") (pin "2") (pinfunction "2_2") (pintype "passive"))
      (node (ref "C28") (pin "1") (pinfunction "1_1") (pintype "passive"))
      (node (ref "C29") (pin "2") (pinfunction "2_2") (pintype "passive"))
      (node (ref "C3") (pin "1") (pinfunction "1_1") (pintype "passive"))
      (node (ref "C30") (pin "2") (pinfunction "2_2") (pintype "passive"))
      (node (ref "C31") (pin "2") (pinfunction "2_2") (pintype "passive"))
      (node (ref "C33") (pin "2") (pinfunction "2_2") (pintype "passive"))
      (node (ref "C35") (pin "2") (pinfunction "2_2") (pintype "passive"))
      (node (ref "C4") (pin "2") (pinfunction "2_2") (pintype "passive"))
      (node (ref "C5") (pin "2") (pinfunction "2_2") (pintype "passive"))
      (node (ref "C6") (pin "2") (pinfunction "2_2") (pintype "passive"))
      (node (ref "C7") (pin "2") (pinfunction "2_2") (pintype "passive"))
      (node (ref "C8") (pin "2") (pinfunction "2_2") (pintype "passive"))
      (node (ref "C9") (pin "2") (pinfunction "2_2") (pintype "passive"))
      (node (ref "D1") (pin "A") (pinfunction "A_A") (pintype "passive"))
      (node (ref "D100") (pin "3") (pinfunction "CC_3") (pintype "bidirectional"))
      (node (ref "D101") (pin "3") (pinfunction "CC_3") (pintype "bidirectional"))
      (node (ref "GPIO") (pin "14") (pinfunction "14_14") (pintype "passive"))
      (node (ref "GPIO") (pin "20") (pinfunction "20_20") (pintype "passive"))
      (node (ref "GPIO") (pin "25") (pinfunction "25_25") (pintype "passive"))
      (node (ref "GPIO") (pin "30") (pinfunction "30_30") (pintype "passive"))
      (node (ref "GPIO") (pin "34") (pinfunction "34_34") (pintype "passive"))
      (node (ref "GPIO") (pin "39") (pinfunction "39_39") (pintype "passive"))
      (node (ref "GPIO") (pin "6") (pinfunction "6_6") (pintype "passive"))
      (node (ref "GPIO") (pin "9") (pinfunction "9_9") (pintype "passive"))
      (node (ref "IC1") (pin "1") (pinfunction "A0_1") (pintype "input"))
      (node (ref "IC1") (pin "2") (pinfunction "A1_2") (pintype "input"))
      (node (ref "IC1") (pin "3") (pinfunction "A2_3") (pintype "input"))
      (node (ref "IC1") (pin "4") (pinfunction "GND_4") (pintype "power_in"))
      (node (ref "IC100") (pin "1") (pinfunction "GND_1") (pintype "input"))
      (node (ref "IC2") (pin "10") (pinfunction "NC_10") (pintype "bidirectional"))
      (node (ref "IC2") (pin "11") (pinfunction "NC_11") (pintype "bidirectional"))
      (node (ref "IC2") (pin "12") (pinfunction "NC_12") (pintype "bidirectional"))
      (node (ref "IC2") (pin "13") (pinfunction "GND_13") (pintype "bidirectional"))
      (node (ref "IC2") (pin "5") (pinfunction "NC_5") (pintype "bidirectional"))
      (node (ref "IC2") (pin "6") (pinfunction "NC_6") (pintype "bidirectional"))
      (node (ref "IC2") (pin "7") (pinfunction "NC_7") (pintype "bidirectional"))
      (node (ref "IC2") (pin "8") (pinfunction "NC_8") (pintype "bidirectional"))
      (node (ref "IC2") (pin "9") (pinfunction "NC_9") (pintype "bidirectional"))
      (node (ref "JP2") (pin "3") (pinfunction "3_3") (pintype "passive"))
      (node (ref "JP4") (pin "4") (pinfunction "4_4") (pintype "passive"))
      (node (ref "L100") (pin "1") (pinfunction "1_1") (pintype "passive"))
      (node (ref "L3") (pin "1") (pinfunction "1_1") (pintype "passive"))
      (node (ref "OOBD2-CONNECTOR1") (pin "3") (pinfunction "3_3") (pintype "passive"))
      (node (ref "PWR_LED") (pin "C") (pinfunction "C_C") (pintype "passive"))
      (node (ref "R101") (pin "2") (pinfunction "2_2") (pintype "passive"))
      (node (ref "R102") (pin "2") (pinfunction "2_2") (pintype "passive"))
      (node (ref "R105") (pin "1") (pinfunction "1_1") (pintype "passive"))
      (node (ref "R108") (pin "1") (pinfunction "1_1") (pintype "passive"))
      (node (ref "R112") (pin "2") (pinfunction "2_2") (pintype "passive"))
      (node (ref "R116") (pin "2") (pinfunction "2_2") (pintype "passive"))
      (node (ref "R13") (pin "1") (pinfunction "1_1") (pintype "passive"))
      (node (ref "R5") (pin "1") (pinfunction "1_1") (pintype "passive"))
      (node (ref "R7") (pin "1") (pinfunction "1_1") (pintype "passive"))
      (node (ref "SJ1") (pin "1") (pinfunction "1_1") (pintype "passive"))
      (node (ref "U$100") (pin "23") (pinfunction "VSS1_23") (pintype "power_in"))
      (node (ref "U$100") (pin "35") (pinfunction "VSS2_35") (pintype "power_in"))
      (node (ref "U$100") (pin "47") (pinfunction "VSS3_47") (pintype "power_in"))
      (node (ref "U$100") (pin "8") (pinfunction "VSSA_8") (pintype "power_in"))
      (node (ref "U$101") (pin "14") (pinfunction "TEST/SCL_14") (pintype "bidirectional"))
      (node (ref "U$101") (pin "15") (pinfunction "GND_15") (pintype "bidirectional"))
      (node (ref "U$102") (pin "23") (pinfunction "VSS1_23") (pintype "power_in"))
      (node (ref "U$102") (pin "35") (pinfunction "VSS2_35") (pintype "power_in"))
      (node (ref "U$102") (pin "47") (pinfunction "VSS3_47") (pintype "power_in"))
      (node (ref "U$102") (pin "8") (pinfunction "VSSA_8") (pintype "power_in"))
      (node (ref "U1") (pin "11") (pinfunction "GND_11") (pintype "power_in"))
      (node (ref "U1") (pin "15") (pinfunction "GND_15") (pintype "power_in"))
      (node (ref "U1") (pin "3") (pinfunction "GND_3") (pintype "power_in"))
      (node (ref "U1") (pin "THERMAL") (pinfunction "GND_THERMAL") (pintype "power_in"))
      (node (ref "U100") (pin "2") (pinfunction "GND_2") (pintype "power_in"))
      (node (ref "U101") (pin "2") (pinfunction "VSS_2") (pintype "power_in"))
      (node (ref "U102") (pin "2") (pinfunction "VSS_2") (pintype "power_in"))
      (node (ref "U2") (pin "4") (pinfunction "GND_4") (pintype "bidirectional"))
      (node (ref "USB_HOST1") (pin "4") (pinfunction "4_4") (pintype "passive"))
      (node (ref "USB_HOST100") (pin "4") (pinfunction "4_4") (pintype "input"))
    )
    (net (code "9") (name "HS-CAN_H") (class "Default")
      (node (ref "D101") (pin "2") (pinfunction "C2_2") (pintype "bidirectional"))
      (node (ref "OOBD2-CONNECTOR1") (pin "7") (pinfunction "7_7") (pintype "passive"))
      (node (ref "R111") (pin "2") (pinfunction "2_2") (pintype "passive"))
      (node (ref "U102") (pin "7") (pinfunction "CANH_7") (pintype "output"))
    )
    (net (code "10") (name "HS-CAN_L") (class "Default")
      (node (ref "D101") (pin "1") (pinfunction "C1_1") (pintype "bidirectional"))
      (node (ref "HS-CAN_TERM") (pin "1") (pinfunction "1_1") (pintype "passive"))
      (node (ref "OOBD2-CONNECTOR1") (pin "6") (pinfunction "6_6") (pintype "passive"))
      (node (ref "U102") (pin "6") (pinfunction "CANL_6") (pintype "output"))
    )
    (net (code "11") (name "ID_SC") (class "Default")
      (node (ref "GPIO") (pin "28") (pinfunction "28_28") (pintype "passive"))
      (node (ref "IC1") (pin "6") (pinfunction "SCL_6") (pintype "input"))
      (node (ref "R4") (pin "2") (pinfunction "2_2") (pintype "passive"))
    )
    (net (code "12") (name "ID_SD") (class "Default")
      (node (ref "GPIO") (pin "27") (pinfunction "27_27") (pintype "passive"))
      (node (ref "IC1") (pin "5") (pinfunction "SDA_5") (pintype "bidirectional"))
      (node (ref "R9") (pin "2") (pinfunction "2_2") (pintype "passive"))
    )
    (net (code "13") (name "MS-CAN_H") (class "Default")
      (node (ref "D100") (pin "2") (pinfunction "C2_2") (pintype "bidirectional"))
      (node (ref "OOBD2-CONNECTOR1") (pin "1") (pinfunction "1_1") (pintype "passive"))
      (node (ref "R109") (pin "2") (pinfunction "2_2") (pintype "passive"))
      (node (ref "U101") (pin "7") (pinfunction "CANH_7") (pintype "output"))
    )
    (net (code "14") (name "MS-CAN_L") (class "Default")
      (node (ref "D100") (pin "1") (pinfunction "C1_1") (pintype "bidirectional"))
      (node (ref "MS-CAN_TERM") (pin "1") (pinfunction "1_1") (pintype "passive"))
      (node (ref "OOBD2-CONNECTOR1") (pin "2") (pinfunction "2_2") (pintype "passive"))
      (node (ref "U101") (pin "6") (pinfunction "CANL_6") (pintype "output"))
    )
    (net (code "15") (name "Net-(BAT100-+)") (class "Default")
      (node (ref "BAT100") (pin "VCC@1") (pinfunction "+_VCC@1") (pintype "power_in"))
      (node (ref "IC2") (pin "14") (pinfunction "VBAT_14") (pintype "bidirectional"))
    )
    (net (code "16") (name "Net-(C29-Pad1)") (class "Default")
      (node (ref "C29") (pin "1") (pinfunction "1_1") (pintype "passive"))
      (node (ref "C31") (pin "1") (pinfunction "1_1") (pintype "passive"))
      (node (ref "L4") (pin "1") (pinfunction "1_1") (pintype "passive"))
      (node (ref "R21") (pin "1") (pinfunction "1_1") (pintype "passive"))
    )
    (net (code "17") (name "Net-(C33-Pad1)") (class "Default")
      (node (ref "C33") (pin "1") (pinfunction "1_1") (pintype "passive"))
      (node (ref "L5") (pin "2") (pinfunction "2_2") (pintype "passive"))
      (node (ref "USB_HOST1") (pin "1") (pinfunction "1_1") (pintype "passive"))
    )
    (net (code "18") (name "Net-(C34-Pad2)") (class "Default")
      (node (ref "C34") (pin "2") (pinfunction "2_2") (pintype "passive"))
      (node (ref "R102") (pin "1") (pinfunction "1_1") (pintype "passive"))
    )
    (net (code "19") (name "Net-(C35-Pad1)") (class "Default")
      (node (ref "C35") (pin "1") (pinfunction "1_1") (pintype "passive"))
      (node (ref "L4") (pin "2") (pinfunction "2_2") (pintype "passive"))
      (node (ref "USB_HOST100") (pin "1") (pinfunction "1_1") (pintype "input"))
    )
    (net (code "20") (name "Net-(C103-Pad1)") (class "Default")
      (node (ref "C103") (pin "1") (pinfunction "1_1") (pintype "passive"))
      (node (ref "R109") (pin "1") (pinfunction "1_1") (pintype "passive"))
      (node (ref "R110") (pin "1") (pinfunction "1_1") (pintype "passive"))
    )
    (net (code "21") (name "Net-(C107-Pad1)") (class "Default")
      (node (ref "C107") (pin "1") (pinfunction "1_1") (pintype "passive"))
      (node (ref "R111") (pin "1") (pinfunction "1_1") (pintype "passive"))
      (node (ref "R114") (pin "1") (pinfunction "1_1") (pintype "passive"))
    )
    (net (code "22") (name "Net-(HS-CAN_TERM-Pad2)") (class "Default")
      (node (ref "HS-CAN_TERM") (pin "2") (pinfunction "2_2") (pintype "passive"))
      (node (ref "R114") (pin "2") (pinfunction "2_2") (pintype "passive"))
    )
    (net (code "23") (name "Net-(IC1-WP)") (class "Default")
      (node (ref "IC1") (pin "7") (pinfunction "WP_7") (pintype "input"))
      (node (ref "R1") (pin "2") (pinfunction "2_2") (pintype "passive"))
      (node (ref "SJ1") (pin "2") (pinfunction "2_2") (pintype "passive"))
    )
    (net (code "24") (name "Net-(IC100-OUT)") (class "Default")
      (node (ref "C1") (pin "1") (pinfunction "1_1") (pintype "passive"))
      (node (ref "IC100") (pin "2") (pinfunction "OUT_2") (pintype "passive"))
      (node (ref "IC100") (pin "TAB") (pinfunction "OUT1_TAB") (pintype "passive"))
      (node (ref "JP1") (pin "2") (pinfunction "2_2") (pintype "passive"))
    )
    (net (code "25") (name "Net-(L3-Pad2)") (class "Default")
      (node (ref "L3") (pin "2") (pinfunction "2_2") (pintype "passive"))
      (node (ref "USB_HOST100") (pin "5") (pinfunction "5_5") (pintype "input"))
    )
    (net (code "26") (name "Net-(LED1-PadC)") (class "Default")
      (node (ref "LED1") (pin "C") (pinfunction "C_C") (pintype "passive"))
      (node (ref "R18") (pin "1") (pinfunction "1_1") (pintype "passive"))
    )
    (net (code "27") (name "Net-(LED100-PadC)") (class "Default")
      (node (ref "LED100") (pin "C") (pinfunction "C_C") (pintype "passive"))
      (node (ref "R19") (pin "1") (pinfunction "1_1") (pintype "passive"))
    )
    (net (code "28") (name "Net-(LED101-PadC)") (class "Default")
      (node (ref "LED101") (pin "C") (pinfunction "C_C") (pintype "passive"))
      (node (ref "R15") (pin "1") (pinfunction "1_1") (pintype "passive"))
    )
    (net (code "29") (name "Net-(LED102-PadC)") (class "Default")
      (node (ref "LED102") (pin "C") (pinfunction "C_C") (pintype "passive"))
      (node (ref "R10") (pin "1") (pinfunction "1_1") (pintype "passive"))
    )
    (net (code "30") (name "Net-(LED103-PadC)") (class "Default")
      (node (ref "LED103") (pin "C") (pinfunction "C_C") (pintype "passive"))
      (node (ref "R6") (pin "1") (pinfunction "1_1") (pintype "passive"))
    )
    (net (code "31") (name "Net-(LED104-PadC)") (class "Default")
      (node (ref "LED104") (pin "C") (pinfunction "C_C") (pintype "passive"))
      (node (ref "R3") (pin "1") (pinfunction "1_1") (pintype "passive"))
    )
    (net (code "32") (name "Net-(MS-CAN_TERM-Pad2)") (class "Default")
      (node (ref "MS-CAN_TERM") (pin "2") (pinfunction "2_2") (pintype "passive"))
      (node (ref "R110") (pin "2") (pinfunction "2_2") (pintype "passive"))
    )
    (net (code "33") (name "Net-(PP1-TP)") (class "Default")
      (node (ref "PP1") (pin "P$1") (pinfunction "TP_P$1") (pintype "input"))
      (node (ref "R20") (pin "2") (pinfunction "2_2") (pintype "passive"))
      (node (ref "U$101") (pin "26") (pinfunction "DP0_26") (pintype "bidirectional"))
    )
    (net (code "34") (name "Net-(PP2-TP)") (class "Default")
      (node (ref "PP2") (pin "P$1") (pinfunction "TP_P$1") (pintype "input"))
      (node (ref "R22") (pin "2") (pinfunction "2_2") (pintype "passive"))
      (node (ref "U$101") (pin "25") (pinfunction "DM0_25") (pintype "bidirectional"))
    )
    (net (code "35") (name "Net-(PWR_LED-PadA)") (class "Default")
      (node (ref "PWR_LED") (pin "A") (pinfunction "A_A") (pintype "passive"))
      (node (ref "R12") (pin "2") (pinfunction "2_2") (pintype "passive"))
    )
    (net (code "36") (name "Net-(R20-Pad1)") (class "Default")
      (node (ref "R20") (pin "1") (pinfunction "1_1") (pintype "passive"))
      (node (ref "USB_HOST100") (pin "3") (pinfunction "3_3") (pintype "input"))
    )
    (net (code "37") (name "Net-(R22-Pad1)") (class "Default")
      (node (ref "R22") (pin "1") (pinfunction "1_1") (pintype "passive"))
      (node (ref "USB_HOST100") (pin "2") (pinfunction "2_2") (pintype "input"))
    )
    (net (code "38") (name "Net-(U$100-NRST)") (class "Default")
      (node (ref "C110") (pin "2") (pinfunction "2_2") (pintype "passive"))
      (node (ref "R104") (pin "2") (pinfunction "2_2") (pintype "passive"))
      (node (ref "U$100") (pin "7") (pinfunction "NRST_7") (pintype "bidirectional"))
    )
    (net (code "39") (name "Net-(U$100-PA0)") (class "Default")
      (node (ref "R6") (pin "2") (pinfunction "2_2") (pintype "passive"))
      (node (ref "U$100") (pin "10") (pinfunction "PA0_10") (pintype "bidirectional"))
    )
    (net (code "40") (name "Net-(U$100-PA1)") (class "Default")
      (node (ref "R10") (pin "2") (pinfunction "2_2") (pintype "passive"))
      (node (ref "U$100") (pin "11") (pinfunction "PA1_11") (pintype "bidirectional"))
    )
    (net (code "41") (name "Net-(U$100-PA2)") (class "Default")
      (node (ref "R3") (pin "2") (pinfunction "2_2") (pintype "passive"))
      (node (ref "U$100") (pin "12") (pinfunction "PA2_12") (pintype "bidirectional"))
    )
    (net (code "42") (name "Net-(U$100-PB8)") (class "Default")
      (node (ref "U$100") (pin "45") (pinfunction "PB8_45") (pintype "bidirectional"))
      (node (ref "U102") (pin "4") (pinfunction "RXD_4") (pintype "output"))
    )
    (net (code "43") (name "Net-(U$100-PB9)") (class "Default")
      (node (ref "U$100") (pin "46") (pinfunction "PB9_46") (pintype "bidirectional"))
      (node (ref "U102") (pin "1") (pinfunction "TXD_1") (pintype "input"))
    )
    (net (code "44") (name "Net-(U$100-PC13)") (class "Default")
      (node (ref "R113") (pin "1") (pinfunction "1_1") (pintype "passive"))
      (node (ref "U$100") (pin "2") (pinfunction "PC13_2") (pintype "bidirectional"))
      (node (ref "U102") (pin "8") (pinfunction "RS_8") (pintype "input"))
    )
    (net (code "45") (name "Net-(U$100-PF11-BOOT0)") (class "Default")
      (node (ref "R112") (pin "1") (pinfunction "1_1") (pintype "passive"))
      (node (ref "U$100") (pin "44") (pinfunction "PF11-BOOT0_44") (pintype "bidirectional"))
    )
    (net (code "46") (name "Net-(U$101-AVDD)") (class "Default")
      (node (ref "C11") (pin "1") (pinfunction "1_1") (pintype "passive"))
      (node (ref "C8") (pin "1") (pinfunction "1_1") (pintype "passive"))
      (node (ref "C9") (pin "1") (pinfunction "1_1") (pintype "passive"))
      (node (ref "L1") (pin "1") (pinfunction "1_1") (pintype "passive"))
      (node (ref "U$101") (pin "1") (pinfunction "AVDD_1") (pintype "bidirectional"))
      (node (ref "U$101") (pin "10") (pinfunction "AVDD3_10") (pintype "bidirectional"))
      (node (ref "U$101") (pin "5") (pinfunction "AVDD2_5") (pintype "bidirectional"))
    )
    (net (code "47") (name "Net-(U$101-DVDD)") (class "Default")
      (node (ref "C10") (pin "+") (pinfunction "+_+") (pintype "passive"))
      (node (ref "C17") (pin "1") (pinfunction "1_1") (pintype "passive"))
      (node (ref "L1") (pin "2") (pinfunction "2_2") (pintype "passive"))
      (node (ref "R14") (pin "2") (pinfunction "2_2") (pintype "passive"))
      (node (ref "R16") (pin "2") (pinfunction "2_2") (pintype "passive"))
      (node (ref "U$101") (pin "16") (pinfunction "DVDD_16") (pintype "bidirectional"))
      (node (ref "U$101") (pin "24") (pinfunction "V33_24") (pintype "bidirectional"))
    )
    (net (code "48") (name "Net-(U$101-PGANG)") (class "Default")
      (node (ref "R14") (pin "1") (pinfunction "1_1") (pintype "passive"))
      (node (ref "U$101") (pin "18") (pinfunction "PGANG_18") (pintype "bidirectional"))
    )
    (net (code "49") (name "Net-(U$101-PSELF)") (class "Default")
      (node (ref "R16") (pin "1") (pinfunction "1_1") (pintype "passive"))
      (node (ref "U$101") (pin "17") (pinfunction "PSELF_17") (pintype "bidirectional"))
    )
    (net (code "50") (name "Net-(U$101-RESET#)") (class "Default")
      (node (ref "C12") (pin "1") (pinfunction "1_1") (pintype "passive"))
      (node (ref "R11") (pin "2") (pinfunction "2_2") (pintype "passive"))
      (node (ref "R7") (pin "2") (pinfunction "2_2") (pintype "passive"))
      (node (ref "U$101") (pin "13") (pinfunction "RESET#_13") (pintype "bidirectional"))
    )
    (net (code "51") (name "Net-(U$101-RREF)") (class "Default")
      (node (ref "R5") (pin "2") (pinfunction "2_2") (pintype "passive"))
      (node (ref "U$101") (pin "4") (pinfunction "RREF_4") (pintype "bidirectional"))
    )
    (net (code "52") (name "Net-(U$101-X1)") (class "Default")
      (node (ref "C13") (pin "1") (pinfunction "1_1") (pintype "passive"))
      (node (ref "Q1") (pin "1") (pinfunction "1_1") (pintype "passive"))
      (node (ref "U$101") (pin "6") (pinfunction "X1_6") (pintype "bidirectional"))
    )
    (net (code "53") (name "Net-(U$101-X2)") (class "Default")
      (node (ref "C16") (pin "1") (pinfunction "1_1") (pintype "passive"))
      (node (ref "Q1") (pin "2") (pinfunction "2_2") (pintype "passive"))
      (node (ref "U$101") (pin "7") (pinfunction "X2_7") (pintype "bidirectional"))
    )
    (net (code "54") (name "Net-(U$102-NRST)") (class "Default")
      (node (ref "C21") (pin "2") (pinfunction "2_2") (pintype "passive"))
      (node (ref "R115") (pin "2") (pinfunction "2_2") (pintype "passive"))
      (node (ref "U$102") (pin "7") (pinfunction "NRST_7") (pintype "bidirectional"))
    )
    (net (code "55") (name "Net-(U$102-PA0)") (class "Default")
      (node (ref "R15") (pin "2") (pinfunction "2_2") (pintype "passive"))
      (node (ref "U$102") (pin "10") (pinfunction "PA0_10") (pintype "bidirectional"))
    )
    (net (code "56") (name "Net-(U$102-PA1)") (class "Default")
      (node (ref "R18") (pin "2") (pinfunction "2_2") (pintype "passive"))
      (node (ref "U$102") (pin "11") (pinfunction "PA1_11") (pintype "bidirectional"))
    )
    (net (code "57") (name "Net-(U$102-PA2)") (class "Default")
      (node (ref "R19") (pin "2") (pinfunction "2_2") (pintype "passive"))
      (node (ref "U$102") (pin "12") (pinfunction "PA2_12") (pintype "bidirectional"))
    )
    (net (code "58") (name "Net-(U$102-PB8)") (class "Default")
      (node (ref "U$102") (pin "45") (pinfunction "PB8_45") (pintype "bidirectional"))
      (node (ref "U101") (pin "4") (pinfunction "RXD_4") (pintype "output"))
    )
    (net (code "59") (name "Net-(U$102-PB9)") (class "Default")
      (node (ref "U$102") (pin "46") (pinfunction "PB9_46") (pintype "bidirectional"))
      (node (ref "U101") (pin "1") (pinfunction "TXD_1") (pintype "input"))
    )
    (net (code "60") (name "Net-(U$102-PC13)") (class "Default")
      (node (ref "R106") (pin "1") (pinfunction "1_1") (pintype "passive"))
      (node (ref "U$102") (pin "2") (pinfunction "PC13_2") (pintype "bidirectional"))
      (node (ref "U101") (pin "8") (pinfunction "RS_8") (pintype "input"))
    )
    (net (code "61") (name "Net-(U$102-PF11-BOOT0)") (class "Default")
      (node (ref "R116") (pin "1") (pinfunction "1_1") (pintype "passive"))
      (node (ref "U$102") (pin "44") (pinfunction "PF11-BOOT0_44") (pintype "bidirectional"))
    )
    (net (code "62") (name "Net-(U1-GAIN)") (class "Default")
      (node (ref "R13") (pin "2") (pinfunction "2_2") (pintype "passive"))
      (node (ref "R17") (pin "1") (pinfunction "1_1") (pintype "passive"))
      (node (ref "U1") (pin "2") (pinfunction "GAIN_2") (pintype "bidirectional"))
    )
    (net (code "63") (name "Net-(U1-OUTN)") (class "Default")
      (node (ref "C15") (pin "2") (pinfunction "2_2") (pintype "passive"))
      (node (ref "JP3") (pin "2") (pinfunction "2_2") (pintype "passive"))
      (node (ref "U1") (pin "10") (pinfunction "OUTN_10") (pintype "output"))
    )
    (net (code "64") (name "Net-(U1-OUTP)") (class "Default")
      (node (ref "C20") (pin "2") (pinfunction "2_2") (pintype "passive"))
      (node (ref "JP3") (pin "1") (pinfunction "1_1") (pintype "passive"))
      (node (ref "U1") (pin "9") (pinfunction "OUTP_9") (pintype "output"))
    )
    (net (code "65") (name "Net-(U2-BS)") (class "Default")
      (node (ref "C32") (pin "1") (pinfunction "1_1") (pintype "passive"))
      (node (ref "U2") (pin "1") (pinfunction "BS_1") (pintype "bidirectional"))
    )
    (net (code "66") (name "Net-(U2-COMP)") (class "Default")
      (node (ref "C34") (pin "1") (pinfunction "1_1") (pintype "passive"))
      (node (ref "U2") (pin "6") (pinfunction "COMP_6") (pintype "bidirectional"))
    )
    (net (code "67") (name "Net-(U2-EN)") (class "Default")
      (node (ref "R24") (pin "2") (pinfunction "2_2") (pintype "passive"))
      (node (ref "U2") (pin "7") (pinfunction "EN_7") (pintype "bidirectional"))
    )
    (net (code "68") (name "Net-(U2-FB)") (class "Default")
      (node (ref "R101") (pin "1") (pinfunction "1_1") (pintype "passive"))
      (node (ref "R25") (pin "1") (pinfunction "1_1") (pintype "passive"))
      (node (ref "U2") (pin "5") (pinfunction "FB_5") (pintype "bidirectional"))
    )
    (net (code "69") (name "Net-(U2-SS)") (class "Default")
      (node (ref "C27") (pin "1") (pinfunction "1_1") (pintype "passive"))
      (node (ref "U2") (pin "8") (pinfunction "SS_8") (pintype "bidirectional"))
    )
    (net (code "70") (name "Net-(U2-SW)") (class "Default")
      (node (ref "C32") (pin "2") (pinfunction "2_2") (pintype "passive"))
      (node (ref "L2") (pin "1") (pinfunction "1_1") (pintype "passive"))
      (node (ref "U2") (pin "3") (pinfunction "SW_3") (pintype "bidirectional"))
    )
    (net (code "71") (name "Net-(U100-EN)") (class "Default")
      (node (ref "R100") (pin "1") (pinfunction "1_1") (pintype "passive"))
      (node (ref "R103") (pin "1") (pinfunction "1_1") (pintype "passive"))
      (node (ref "R105") (pin "2") (pinfunction "2_2") (pintype "passive"))
      (node (ref "U100") (pin "4") (pinfunction "EN_4") (pintype "bidirectional"))
    )
    (net (code "72") (name "Net-(U100-ISET)") (class "Default")
      (node (ref "R108") (pin "2") (pinfunction "2_2") (pintype "passive"))
      (node (ref "U100") (pin "3") (pinfunction "ISET_3") (pintype "bidirectional"))
    )
    (net (code "73") (name "Net-(U100-OUT)") (class "Default")
      (node (ref "C100") (pin "1") (pinfunction "1_1") (pintype "passive"))
      (node (ref "C104") (pin "1") (pinfunction "1_1") (pintype "passive"))
      (node (ref "L5") (pin "1") (pinfunction "1_1") (pintype "passive"))
      (node (ref "R107") (pin "2") (pinfunction "2_2") (pintype "passive"))
      (node (ref "U100") (pin "1") (pinfunction "OUT_1") (pintype "bidirectional"))
    )
    (net (code "74") (name "Net-(USB_HOST1-5)") (class "Default")
      (node (ref "L100") (pin "2") (pinfunction "2_2") (pintype "passive"))
      (node (ref "USB_HOST1") (pin "P$1") (pinfunction "5_P$1") (pintype "input"))
      (node (ref "USB_HOST1") (pin "P$2") (pinfunction "6_P$2") (pintype "input"))
    )
    (net (code "75") (name "SCL") (class "Default")
      (node (ref "GPIO") (pin "5") (pinfunction "5_5") (pintype "passive"))
      (node (ref "IC2") (pin "16") (pinfunction "SCL_16") (pintype "bidirectional"))
      (node (ref "R23") (pin "2") (pinfunction "2_2") (pintype "passive"))
    )
    (net (code "76") (name "SDA") (class "Default")
      (node (ref "GPIO") (pin "3") (pinfunction "3_3") (pintype "passive"))
      (node (ref "IC2") (pin "15") (pinfunction "SDA_15") (pintype "bidirectional"))
      (node (ref "R2") (pin "2") (pinfunction "2_2") (pintype "passive"))
    )
    (net (code "77") (name "SWCLK") (class "Default")
      (node (ref "JP4") (pin "3") (pinfunction "3_3") (pintype "passive"))
      (node (ref "JP5") (pin "2") (pinfunction "2_2") (pintype "passive"))
      (node (ref "U$100") (pin "37") (pinfunction "PA14_37") (pintype "bidirectional"))
      (node (ref "U$102") (pin "37") (pinfunction "PA14_37") (pintype "bidirectional"))
    )
    (net (code "78") (name "SWDIO") (class "Default")
      (node (ref "JP4") (pin "2") (pinfunction "2_2") (pintype "passive"))
      (node (ref "JP5") (pin "1") (pinfunction "1_1") (pintype "passive"))
      (node (ref "U$100") (pin "34") (pinfunction "PA13_34") (pintype "bidirectional"))
      (node (ref "U$102") (pin "34") (pinfunction "PA13_34") (pintype "bidirectional"))
    )
    (net (code "79") (name "UART0_RXD") (class "Default")
      (node (ref "GPIO") (pin "10") (pinfunction "10_10") (pintype "passive"))
      (node (ref "JP2") (pin "2") (pinfunction "2_2") (pintype "passive"))
    )
    (net (code "80") (name "UART0_TXD") (class "Default")
      (node (ref "GPIO") (pin "8") (pinfunction "8_8") (pintype "passive"))
      (node (ref "JP2") (pin "1") (pinfunction "1_1") (pintype "passive"))
    )
    (net (code "81") (name "USB0_DM") (class "Default")
      (node (ref "U$100") (pin "32") (pinfunction "PA11_32") (pintype "bidirectional"))
      (node (ref "U$101") (pin "27") (pinfunction "DM1_27") (pintype "bidirectional"))
    )
    (net (code "82") (name "USB0_DP") (class "Default")
      (node (ref "U$100") (pin "33") (pinfunction "PA12_33") (pintype "bidirectional"))
      (node (ref "U$101") (pin "28") (pinfunction "DP1_28") (pintype "bidirectional"))
    )
    (net (code "83") (name "USB1_DM") (class "Default")
      (node (ref "U$101") (pin "2") (pinfunction "DM2_2") (pintype "bidirectional"))
      (node (ref "U$102") (pin "32") (pinfunction "PA11_32") (pintype "bidirectional"))
    )
    (net (code "84") (name "USB1_DP") (class "Default")
      (node (ref "U$101") (pin "3") (pinfunction "DP2_3") (pintype "bidirectional"))
      (node (ref "U$102") (pin "33") (pinfunction "PA12_33") (pintype "bidirectional"))
    )
    (net (code "85") (name "USB2_DM") (class "Default")
      (node (ref "U$101") (pin "8") (pinfunction "DM3_8") (pintype "bidirectional"))
      (node (ref "USB_HOST1") (pin "2") (pinfunction "2_2") (pintype "passive"))
    )
    (net (code "86") (name "USB2_DP") (class "Default")
      (node (ref "U$101") (pin "9") (pinfunction "DP3_9") (pintype "bidirectional"))
      (node (ref "USB_HOST1") (pin "3") (pinfunction "3_3") (pintype "passive"))
    )
    (net (code "87") (name "USB_CE") (class "Default")
      (node (ref "GPIO") (pin "31") (pinfunction "31_31") (pintype "passive"))
      (node (ref "R103") (pin "2") (pinfunction "2_2") (pintype "passive"))
    )
    (net (code "88") (name "USB_VBUS") (class "Default")
      (node (ref "GPIO") (pin "32") (pinfunction "32_32") (pintype "passive"))
      (node (ref "R107") (pin "1") (pinfunction "1_1") (pintype "passive"))
    )
    (net (code "89") (name "unconnected-(GPIO-Pad7)") (class "Default")
      (node (ref "GPIO") (pin "7") (pinfunction "7_7") (pintype "passive"))
    )
    (net (code "90") (name "unconnected-(GPIO-Pad11)") (class "Default")
      (node (ref "GPIO") (pin "11") (pinfunction "11_11") (pintype "passive"))
    )
    (net (code "91") (name "unconnected-(GPIO-Pad12)") (class "Default")
      (node (ref "GPIO") (pin "12") (pinfunction "12_12") (pintype "passive"))
    )
    (net (code "92") (name "unconnected-(GPIO-Pad13)") (class "Default")
      (node (ref "GPIO") (pin "13") (pinfunction "13_13") (pintype "passive"))
    )
    (net (code "93") (name "unconnected-(GPIO-Pad15)") (class "Default")
      (node (ref "GPIO") (pin "15") (pinfunction "15_15") (pintype "passive"))
    )
    (net (code "94") (name "unconnected-(GPIO-Pad16)") (class "Default")
      (node (ref "GPIO") (pin "16") (pinfunction "16_16") (pintype "passive"))
    )
    (net (code "95") (name "unconnected-(GPIO-Pad22)") (class "Default")
      (node (ref "GPIO") (pin "22") (pinfunction "22_22") (pintype "passive"))
    )
    (net (code "96") (name "unconnected-(GPIO-Pad23)") (class "Default")
      (node (ref "GPIO") (pin "23") (pinfunction "23_23") (pintype "passive"))
    )
    (net (code "97") (name "unconnected-(GPIO-Pad24)") (class "Default")
      (node (ref "GPIO") (pin "24") (pinfunction "24_24") (pintype "passive"))
    )
    (net (code "98") (name "unconnected-(GPIO-Pad26)") (class "Default")
      (node (ref "GPIO") (pin "26") (pinfunction "26_26") (pintype "passive"))
    )
    (net (code "99") (name "unconnected-(GPIO-Pad33)") (class "Default")
      (node (ref "GPIO") (pin "33") (pinfunction "33_33") (pintype "passive"))
    )
    (net (code "100") (name "unconnected-(GPIO-Pad35)") (class "Default")
      (node (ref "GPIO") (pin "35") (pinfunction "35_35") (pintype "passive"))
    )
    (net (code "101") (name "unconnected-(GPIO-Pad36)") (class "Default")
      (node (ref "GPIO") (pin "36") (pinfunction "36_36") (pintype "passive"))
    )
    (net (code "102") (name "unconnected-(GPIO-Pad37)") (class "Default")
      (node (ref "GPIO") (pin "37") (pinfunction "37_37") (pintype "passive"))
    )
    (net (code "103") (name "unconnected-(GPIO-Pad38)") (class "Default")
      (node (ref "GPIO") (pin "38") (pinfunction "38_38") (pintype "passive"))
    )
    (net (code "104") (name "unconnected-(GPIO-Pad40)") (class "Default")
      (node (ref "GPIO") (pin "40") (pinfunction "40_40") (pintype "passive"))
    )
    (net (code "105") (name "unconnected-(IC2-32KHZ-Pad1)") (class "Default")
      (node (ref "IC2") (pin "1") (pinfunction "32KHZ_1") (pintype "bidirectional"))
    )
    (net (code "106") (name "unconnected-(IC2-~{INT}-Pad3)") (class "Default")
      (node (ref "IC2") (pin "3") (pinfunction "~{INT}_3") (pintype "bidirectional"))
    )
    (net (code "107") (name "unconnected-(IC2-~{RST}-Pad4)") (class "Default")
      (node (ref "IC2") (pin "4") (pinfunction "~{RST}_4") (pintype "bidirectional"))
    )
    (net (code "108") (name "unconnected-(OOBD2-CONNECTOR1-Pad4)") (class "Default")
      (node (ref "OOBD2-CONNECTOR1") (pin "4") (pinfunction "4_4") (pintype "passive"))
    )
    (net (code "109") (name "unconnected-(OOBD2-CONNECTOR1-Pad5)") (class "Default")
      (node (ref "OOBD2-CONNECTOR1") (pin "5") (pinfunction "5_5") (pintype "passive"))
    )
    (net (code "110") (name "unconnected-(OOBD2-CONNECTOR1-Pad8)") (class "Default")
      (node (ref "OOBD2-CONNECTOR1") (pin "8") (pinfunction "8_8") (pintype "passive"))
    )
    (net (code "111") (name "unconnected-(OOBD2-CONNECTOR1-Pad9)") (class "Default")
      (node (ref "OOBD2-CONNECTOR1") (pin "9") (pinfunction "9_9") (pintype "passive"))
    )
    (net (code "112") (name "unconnected-(U$100-PA3-Pad13)") (class "Default")
      (node (ref "U$100") (pin "13") (pinfunction "PA3_13") (pintype "bidirectional"))
    )
    (net (code "113") (name "unconnected-(U$100-PA4-Pad14)") (class "Default")
      (node (ref "U$100") (pin "14") (pinfunction "PA4_14") (pintype "bidirectional"))
    )
    (net (code "114") (name "unconnected-(U$100-PA5-Pad15)") (class "Default")
      (node (ref "U$100") (pin "15") (pinfunction "PA5_15") (pintype "bidirectional"))
    )
    (net (code "115") (name "unconnected-(U$100-PA6-Pad16)") (class "Default")
      (node (ref "U$100") (pin "16") (pinfunction "PA6_16") (pintype "bidirectional"))
    )
    (net (code "116") (name "unconnected-(U$100-PA7-Pad17)") (class "Default")
      (node (ref "U$100") (pin "17") (pinfunction "PA7_17") (pintype "bidirectional"))
    )
    (net (code "117") (name "unconnected-(U$100-PA8-Pad29)") (class "Default")
      (node (ref "U$100") (pin "29") (pinfunction "PA8_29") (pintype "bidirectional"))
    )
    (net (code "118") (name "unconnected-(U$100-PA9-Pad30)") (class "Default")
      (node (ref "U$100") (pin "30") (pinfunction "PA9_30") (pintype "bidirectional"))
    )
    (net (code "119") (name "unconnected-(U$100-PA10-Pad31)") (class "Default")
      (node (ref "U$100") (pin "31") (pinfunction "PA10_31") (pintype "bidirectional"))
    )
    (net (code "120") (name "unconnected-(U$100-PA15-Pad38)") (class "Default")
      (node (ref "U$100") (pin "38") (pinfunction "PA15_38") (pintype "bidirectional"))
    )
    (net (code "121") (name "unconnected-(U$100-PB0-Pad18)") (class "Default")
      (node (ref "U$100") (pin "18") (pinfunction "PB0_18") (pintype "bidirectional"))
    )
    (net (code "122") (name "unconnected-(U$100-PB1-Pad19)") (class "Default")
      (node (ref "U$100") (pin "19") (pinfunction "PB1_19") (pintype "bidirectional"))
    )
    (net (code "123") (name "unconnected-(U$100-PB2-Pad20)") (class "Default")
      (node (ref "U$100") (pin "20") (pinfunction "PB2_20") (pintype "bidirectional"))
    )
    (net (code "124") (name "unconnected-(U$100-PB3-Pad39)") (class "Default")
      (node (ref "U$100") (pin "39") (pinfunction "PB3_39") (pintype "bidirectional"))
    )
    (net (code "125") (name "unconnected-(U$100-PB4-Pad40)") (class "Default")
      (node (ref "U$100") (pin "40") (pinfunction "PB4_40") (pintype "bidirectional"))
    )
    (net (code "126") (name "unconnected-(U$100-PB5-Pad41)") (class "Default")
      (node (ref "U$100") (pin "41") (pinfunction "PB5_41") (pintype "bidirectional"))
    )
    (net (code "127") (name "unconnected-(U$100-PB6-Pad42)") (class "Default")
      (node (ref "U$100") (pin "42") (pinfunction "PB6_42") (pintype "bidirectional"))
    )
    (net (code "128") (name "unconnected-(U$100-PB7-Pad43)") (class "Default")
      (node (ref "U$100") (pin "43") (pinfunction "PB7_43") (pintype "bidirectional"))
    )
    (net (code "129") (name "unconnected-(U$100-PB10-Pad21)") (class "Default")
      (node (ref "U$100") (pin "21") (pinfunction "PB10_21") (pintype "bidirectional"))
    )
    (net (code "130") (name "unconnected-(U$100-PB11-Pad22)") (class "Default")
      (node (ref "U$100") (pin "22") (pinfunction "PB11_22") (pintype "bidirectional"))
    )
    (net (code "131") (name "unconnected-(U$100-PB12-Pad25)") (class "Default")
      (node (ref "U$100") (pin "25") (pinfunction "PB12_25") (pintype "bidirectional"))
    )
    (net (code "132") (name "unconnected-(U$100-PB13-Pad26)") (class "Default")
      (node (ref "U$100") (pin "26") (pinfunction "PB13_26") (pintype "bidirectional"))
    )
    (net (code "133") (name "unconnected-(U$100-PB14-Pad27)") (class "Default")
      (node (ref "U$100") (pin "27") (pinfunction "PB14_27") (pintype "bidirectional"))
    )
    (net (code "134") (name "unconnected-(U$100-PB15-Pad28)") (class "Default")
      (node (ref "U$100") (pin "28") (pinfunction "PB15_28") (pintype "bidirectional"))
    )
    (net (code "135") (name "unconnected-(U$100-PC14-OSC32_IN-Pad3)") (class "Default")
      (node (ref "U$100") (pin "3") (pinfunction "PC14-OSC32_IN_3") (pintype "bidirectional"))
    )
    (net (code "136") (name "unconnected-(U$100-PC15-OSC32_OUT-Pad4)") (class "Default")
      (node (ref "U$100") (pin "4") (pinfunction "PC15-OSC32_OUT_4") (pintype "bidirectional"))
    )
    (net (code "137") (name "unconnected-(U$100-PF0-OSC_IN-Pad5)") (class "Default")
      (node (ref "U$100") (pin "5") (pinfunction "PF0-OSC_IN_5") (pintype "bidirectional"))
    )
    (net (code "138") (name "unconnected-(U$100-PF1-OSC_OUT-Pad6)") (class "Default")
      (node (ref "U$100") (pin "6") (pinfunction "PF1-OSC_OUT_6") (pintype "bidirectional"))
    )
    (net (code "139") (name "unconnected-(U$101-DM4-Pad11)") (class "Default")
      (node (ref "U$101") (pin "11") (pinfunction "DM4_11") (pintype "bidirectional"))
    )
    (net (code "140") (name "unconnected-(U$101-DP4-Pad12)") (class "Default")
      (node (ref "U$101") (pin "12") (pinfunction "DP4_12") (pintype "bidirectional"))
    )
    (net (code "141") (name "unconnected-(U$101-OVCUR1#{slash}SMC-Pad21)") (class "Default")
      (node (ref "U$101") (pin "21") (pinfunction "OVCUR1#/SMC_21") (pintype "bidirectional"))
    )
    (net (code "142") (name "unconnected-(U$101-OVCUR2#{slash}SMD-Pad19)") (class "Default")
      (node (ref "U$101") (pin "19") (pinfunction "OVCUR2#/SMD_19") (pintype "bidirectional"))
    )
    (net (code "143") (name "unconnected-(U$101-PWREN1#{slash}SDA-Pad22)") (class "Default")
      (node (ref "U$101") (pin "22") (pinfunction "PWREN1#/SDA_22") (pintype "bidirectional"))
    )
    (net (code "144") (name "unconnected-(U$101-PWREN2#-Pad20)") (class "Default")
      (node (ref "U$101") (pin "20") (pinfunction "PWREN2#_20") (pintype "bidirectional"))
    )
    (net (code "145") (name "unconnected-(U$102-PA3-Pad13)") (class "Default")
      (node (ref "U$102") (pin "13") (pinfunction "PA3_13") (pintype "bidirectional"))
    )
    (net (code "146") (name "unconnected-(U$102-PA4-Pad14)") (class "Default")
      (node (ref "U$102") (pin "14") (pinfunction "PA4_14") (pintype "bidirectional"))
    )
    (net (code "147") (name "unconnected-(U$102-PA5-Pad15)") (class "Default")
      (node (ref "U$102") (pin "15") (pinfunction "PA5_15") (pintype "bidirectional"))
    )
    (net (code "148") (name "unconnected-(U$102-PA6-Pad16)") (class "Default")
      (node (ref "U$102") (pin "16") (pinfunction "PA6_16") (pintype "bidirectional"))
    )
    (net (code "149") (name "unconnected-(U$102-PA7-Pad17)") (class "Default")
      (node (ref "U$102") (pin "17") (pinfunction "PA7_17") (pintype "bidirectional"))
    )
    (net (code "150") (name "unconnected-(U$102-PA8-Pad29)") (class "Default")
      (node (ref "U$102") (pin "29") (pinfunction "PA8_29") (pintype "bidirectional"))
    )
    (net (code "151") (name "unconnected-(U$102-PA9-Pad30)") (class "Default")
      (node (ref "U$102") (pin "30") (pinfunction "PA9_30") (pintype "bidirectional"))
    )
    (net (code "152") (name "unconnected-(U$102-PA10-Pad31)") (class "Default")
      (node (ref "U$102") (pin "31") (pinfunction "PA10_31") (pintype "bidirectional"))
    )
    (net (code "153") (name "unconnected-(U$102-PA15-Pad38)") (class "Default")
      (node (ref "U$102") (pin "38") (pinfunction "PA15_38") (pintype "bidirectional"))
    )
    (net (code "154") (name "unconnected-(U$102-PB0-Pad18)") (class "Default")
      (node (ref "U$102") (pin "18") (pinfunction "PB0_18") (pintype "bidirectional"))
    )
    (net (code "155") (name "unconnected-(U$102-PB1-Pad19)") (class "Default")
      (node (ref "U$102") (pin "19") (pinfunction "PB1_19") (pintype "bidirectional"))
    )
    (net (code "156") (name "unconnected-(U$102-PB2-Pad20)") (class "Default")
      (node (ref "U$102") (pin "20") (pinfunction "PB2_20") (pintype "bidirectional"))
    )
    (net (code "157") (name "unconnected-(U$102-PB3-Pad39)") (class "Default")
      (node (ref "U$102") (pin "39") (pinfunction "PB3_39") (pintype "bidirectional"))
    )
    (net (code "158") (name "unconnected-(U$102-PB4-Pad40)") (class "Default")
      (node (ref "U$102") (pin "40") (pinfunction "PB4_40") (pintype "bidirectional"))
    )
    (net (code "159") (name "unconnected-(U$102-PB5-Pad41)") (class "Default")
      (node (ref "U$102") (pin "41") (pinfunction "PB5_41") (pintype "bidirectional"))
    )
    (net (code "160") (name "unconnected-(U$102-PB6-Pad42)") (class "Default")
      (node (ref "U$102") (pin "42") (pinfunction "PB6_42") (pintype "bidirectional"))
    )
    (net (code "161") (name "unconnected-(U$102-PB7-Pad43)") (class "Default")
      (node (ref "U$102") (pin "43") (pinfunction "PB7_43") (pintype "bidirectional"))
    )
    (net (code "162") (name "unconnected-(U$102-PB10-Pad21)") (class "Default")
      (node (ref "U$102") (pin "21") (pinfunction "PB10_21") (pintype "bidirectional"))
    )
    (net (code "163") (name "unconnected-(U$102-PB11-Pad22)") (class "Default")
      (node (ref "U$102") (pin "22") (pinfunction "PB11_22") (pintype "bidirectional"))
    )
    (net (code "164") (name "unconnected-(U$102-PB12-Pad25)") (class "Default")
      (node (ref "U$102") (pin "25") (pinfunction "PB12_25") (pintype "bidirectional"))
    )
    (net (code "165") (name "unconnected-(U$102-PB13-Pad26)") (class "Default")
      (node (ref "U$102") (pin "26") (pinfunction "PB13_26") (pintype "bidirectional"))
    )
    (net (code "166") (name "unconnected-(U$102-PB14-Pad27)") (class "Default")
      (node (ref "U$102") (pin "27") (pinfunction "PB14_27") (pintype "bidirectional"))
    )
    (net (code "167") (name "unconnected-(U$102-PB15-Pad28)") (class "Default")
      (node (ref "U$102") (pin "28") (pinfunction "PB15_28") (pintype "bidirectional"))
    )
    (net (code "168") (name "unconnected-(U$102-PC14-OSC32_IN-Pad3)") (class "Default")
      (node (ref "U$102") (pin "3") (pinfunction "PC14-OSC32_IN_3") (pintype "bidirectional"))
    )
    (net (code "169") (name "unconnected-(U$102-PC15-OSC32_OUT-Pad4)") (class "Default")
      (node (ref "U$102") (pin "4") (pinfunction "PC15-OSC32_OUT_4") (pintype "bidirectional"))
    )
    (net (code "170") (name "unconnected-(U$102-PF0-OSC_IN-Pad5)") (class "Default")
      (node (ref "U$102") (pin "5") (pinfunction "PF0-OSC_IN_5") (pintype "bidirectional"))
    )
    (net (code "171") (name "unconnected-(U$102-PF1-OSC_OUT-Pad6)") (class "Default")
      (node (ref "U$102") (pin "6") (pinfunction "PF1-OSC_OUT_6") (pintype "bidirectional"))
    )
    (net (code "172") (name "unconnected-(U101-VREF-Pad5)") (class "Default")
      (node (ref "U101") (pin "5") (pinfunction "VREF_5") (pintype "output"))
    )
    (net (code "173") (name "unconnected-(U102-VREF-Pad5)") (class "Default")
      (node (ref "U102") (pin "5") (pinfunction "VREF_5") (pintype "output"))
    )
    (net (code "174") (name "unconnected-(USB_HOST100-GND1-PadCASING1)") (class "Default")
      (node (ref "USB_HOST100") (pin "CASING1") (pinfunction "GND1_CASING1") (pintype "bidirectional"))
    )
    (net (code "175") (name "unconnected-(USB_HOST100-GND2-PadCASING2)") (class "Default")
      (node (ref "USB_HOST100") (pin "CASING2") (pinfunction "GND2_CASING2") (pintype "bidirectional"))
    )
    (net (code "176") (name "unconnected-(USB_HOST100-GND3-PadCASING3)") (class "Default")
      (node (ref "USB_HOST100") (pin "CASING3") (pinfunction "GND3_CASING3") (pintype "bidirectional"))
    )
    (net (code "177") (name "unconnected-(USB_HOST100-GND4-PadCASING4)") (class "Default")
      (node (ref "USB_HOST100") (pin "CASING4") (pinfunction "GND4_CASING4") (pintype "bidirectional"))
    )
  )
)
